# core_io3.net
KiCad netlist of a schematic drawn in EAGLE
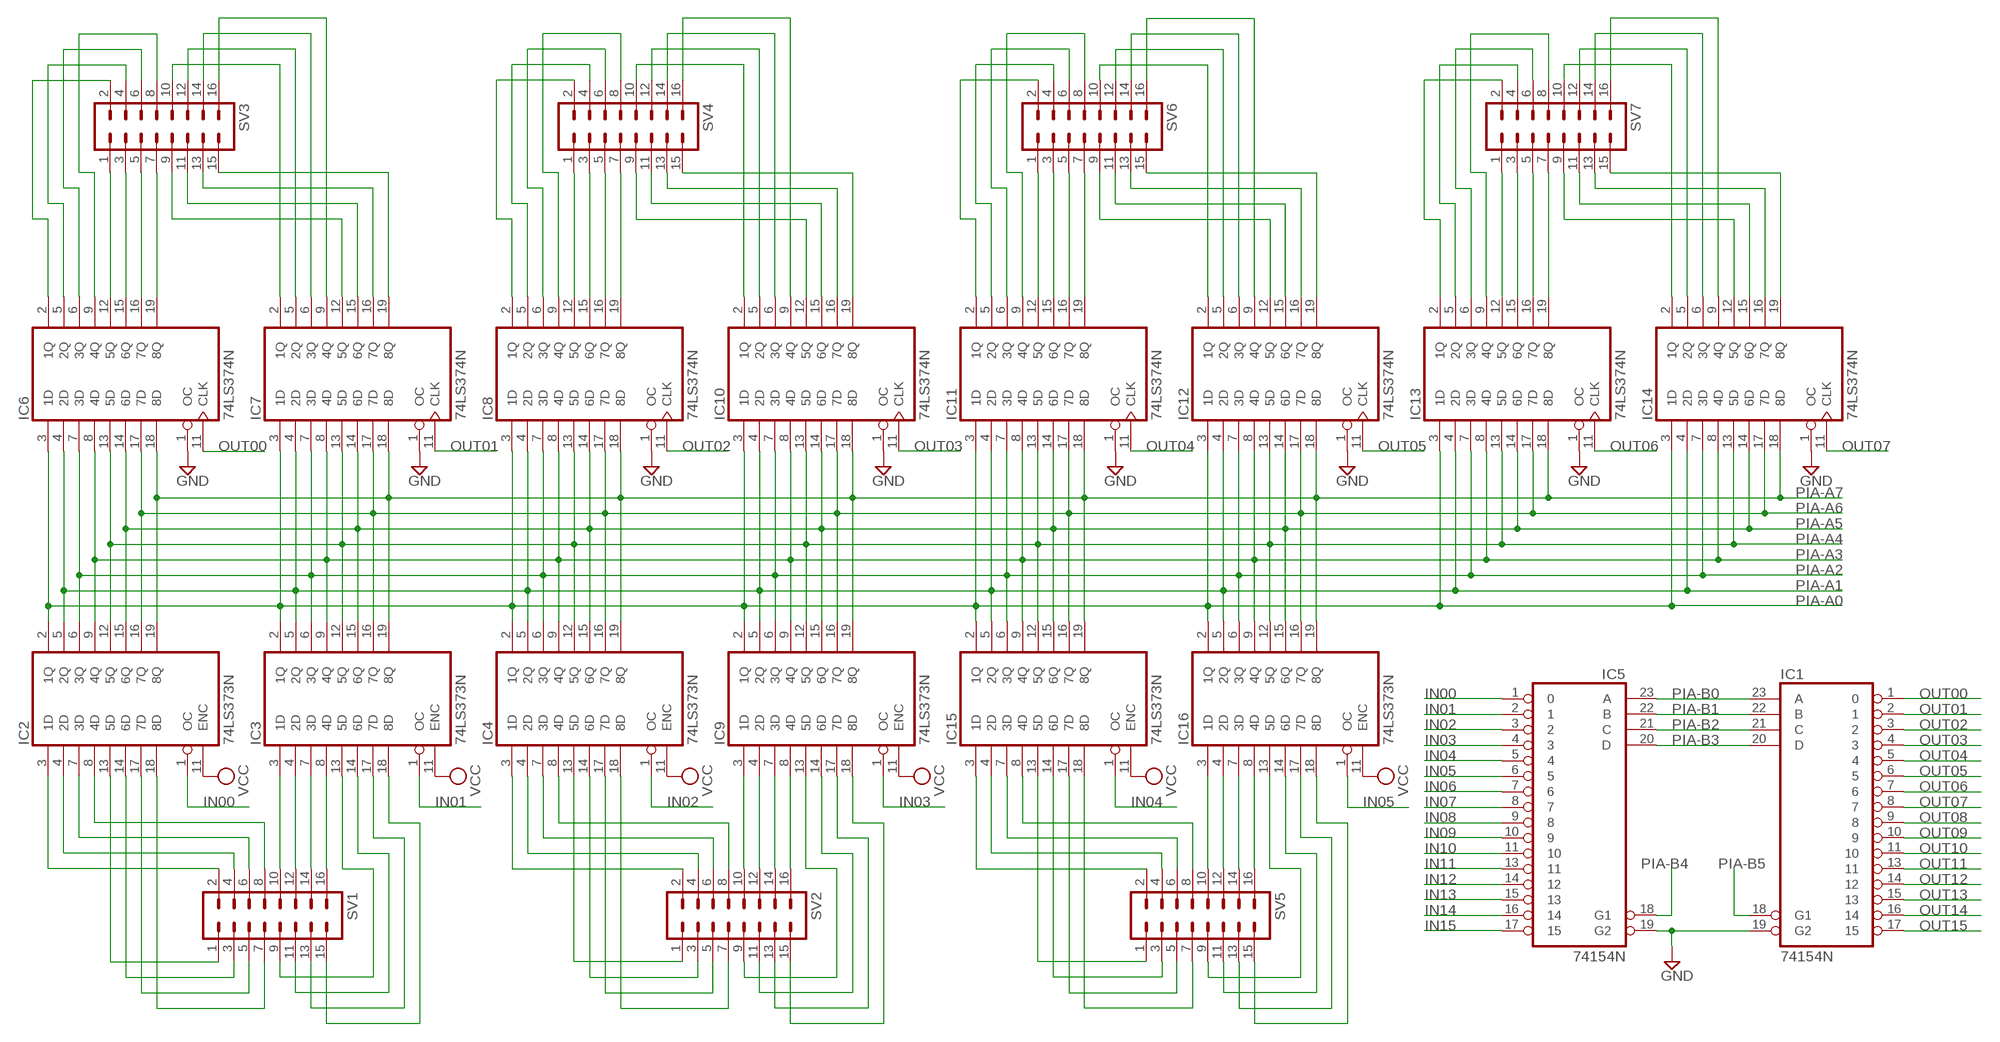
[diagram p0: schematic, sheet 1]
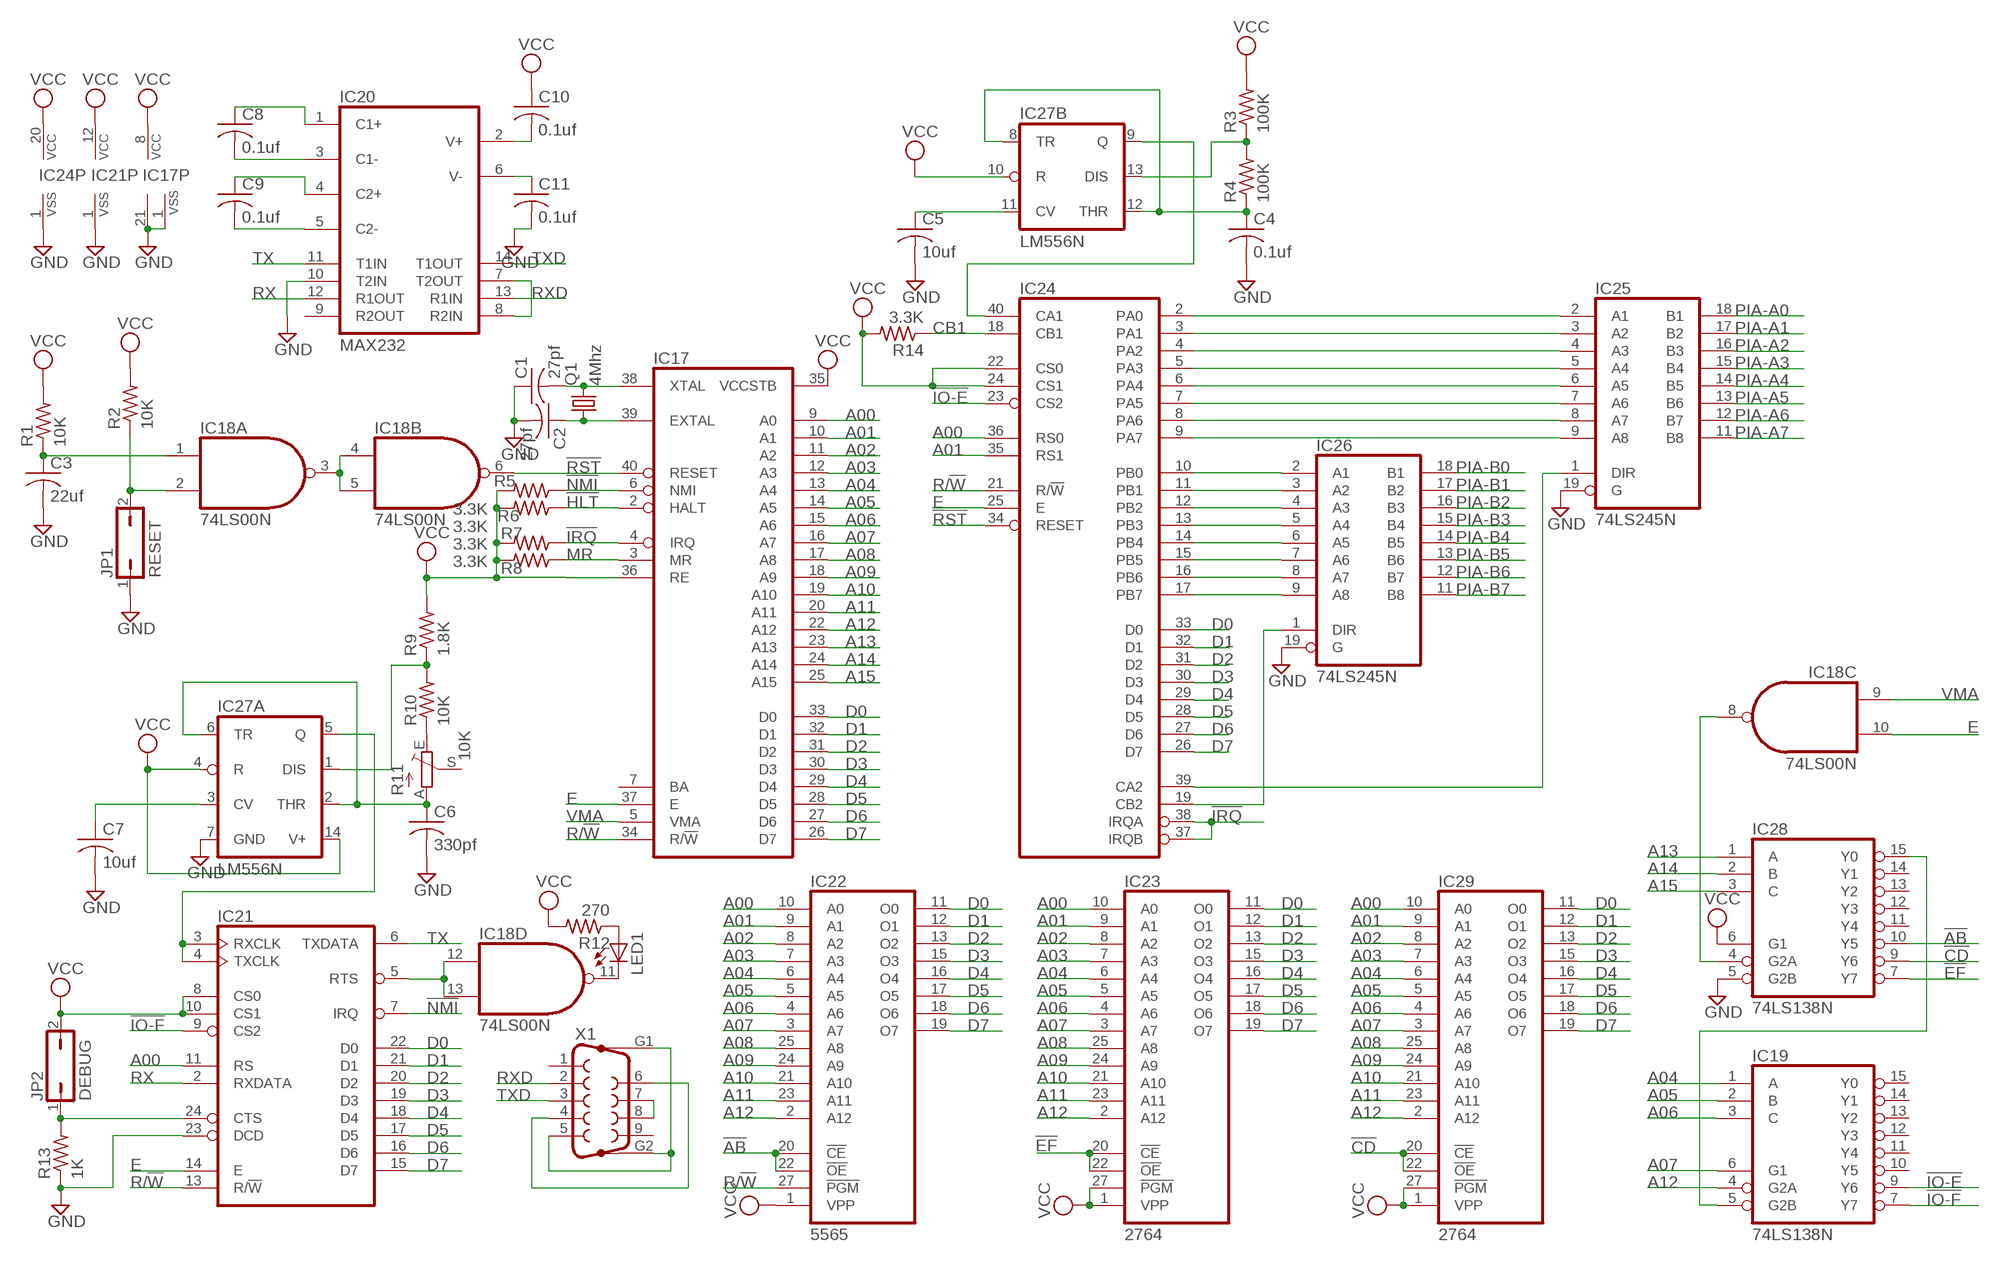
[diagram p1: schematic, sheet 2]
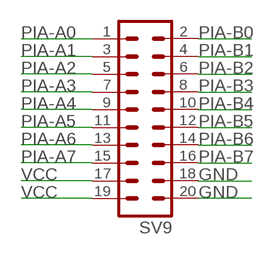
[diagram p2: schematic, sheet 3]

(export (version "E")
  (design (tool "Eeschema 10.0.6"))
  (components
    (comp (ref "C1")
      (value "27pf")
      (footprint "eagle-import:C050-025X075")
      (libsource (lib "eagle-import") (part "C-US050-025X075"))
    )
    (comp (ref "C2")
      (value "27pf")
      (footprint "eagle-import:C050-025X075")
      (libsource (lib "eagle-import") (part "C-US050-025X075"))
    )
    (comp (ref "C3")
      (value "22uf")
      (footprint "eagle-import:C102-043X133")
      (libsource (lib "eagle-import") (part "C-US102-043X133"))
    )
    (comp (ref "C4")
      (value "0.1uf")
      (footprint "eagle-import:C050-025X075")
      (libsource (lib "eagle-import") (part "C-US050-025X075"))
    )
    (comp (ref "C5")
      (value "10uf")
      (footprint "eagle-import:C050-025X075")
      (libsource (lib "eagle-import") (part "C-US050-025X075"))
    )
    (comp (ref "C6")
      (value "330pf")
      (footprint "eagle-import:C050-025X075")
      (libsource (lib "eagle-import") (part "C-US050-025X075"))
    )
    (comp (ref "C7")
      (value "10uf")
      (footprint "eagle-import:C050-025X075")
      (libsource (lib "eagle-import") (part "C-US050-025X075"))
    )
    (comp (ref "C8")
      (value "0.1uf")
      (footprint "eagle-import:C050-025X075")
      (libsource (lib "eagle-import") (part "C-US050-025X075"))
    )
    (comp (ref "C9")
      (value "0.1uf")
      (footprint "eagle-import:C050-025X075")
      (libsource (lib "eagle-import") (part "C-US050-025X075"))
    )
    (comp (ref "C10")
      (value "0.1uf")
      (footprint "eagle-import:C050-025X075")
      (libsource (lib "eagle-import") (part "C-US050-025X075"))
    )
    (comp (ref "C11")
      (value "0.1uf")
      (footprint "eagle-import:C050-025X075")
      (libsource (lib "eagle-import") (part "C-US050-025X075"))
    )
    (comp (ref "IC17")
      (value "6802")
      (footprint "eagle-import:DIL40")
      (libsource (lib "eagle-import") (part "6802"))
    )
    (comp (ref "IC18")
      (value "74LS00N")
      (footprint "eagle-import:DIL14")
      (libsource (lib "eagle-import") (part "7400NLS"))
    )
    (comp (ref "IC19")
      (value "74LS138N")
      (footprint "eagle-import:DIL16")
      (libsource (lib "eagle-import") (part "74138NLS"))
    )
    (comp (ref "IC20")
      (value "MAX232")
      (footprint "eagle-import:DIL16")
      (fields (field (name "MF") "MAXIM") (field (name "MPN") "MAX232ACPE+"))
      (libsource (lib "eagle-import") (part "MAX232"))
    )
    (comp (ref "IC21")
      (value "6850")
      (footprint "eagle-import:DIL24")
      (fields (field (name "MF") "NTE ELECTRONICS") (field (name "MPN") "NTE6850"))
      (libsource (lib "eagle-import") (part "6850"))
    )
    (comp (ref "IC22")
      (value "5565")
      (footprint "eagle-import:DIL28")
      (libsource (lib "eagle-import") (part "2764"))
    )
    (comp (ref "IC23")
      (value "2764")
      (footprint "eagle-import:DIL28")
      (libsource (lib "eagle-import") (part "2764"))
    )
    (comp (ref "IC24")
      (value "6821")
      (footprint "eagle-import:DIL40")
      (fields (field (name "MF") "NTE ELECTRONICS") (field (name "MPN") "NTE6821"))
      (libsource (lib "eagle-import") (part "6821"))
    )
    (comp (ref "IC25")
      (value "74LS245N")
      (footprint "eagle-import:DIL20")
      (libsource (lib "eagle-import") (part "74245NLS"))
    )
    (comp (ref "IC26")
      (value "74LS245N")
      (footprint "eagle-import:DIL20")
      (libsource (lib "eagle-import") (part "74245NLS"))
    )
    (comp (ref "IC27")
      (value "LM556N")
      (footprint "eagle-import:DIL14")
      (libsource (lib "eagle-import") (part "556NLM"))
    )
    (comp (ref "IC28")
      (value "74LS138N")
      (footprint "eagle-import:DIL16")
      (libsource (lib "eagle-import") (part "74138NLS"))
    )
    (comp (ref "IC29")
      (value "2764")
      (footprint "eagle-import:DIL28")
      (libsource (lib "eagle-import") (part "2764"))
    )
    (comp (ref "JP1")
      (value "RESET")
      (footprint "eagle-import:JP1")
      (libsource (lib "eagle-import") (part "JP1Q"))
    )
    (comp (ref "JP2")
      (value "DEBUG")
      (footprint "eagle-import:JP1")
      (libsource (lib "eagle-import") (part "JP1Q"))
    )
    (comp (ref "LED1")
      (value "LED3MM")
      (footprint "eagle-import:LED3MM")
      (libsource (lib "eagle-import") (part "LED3MM"))
    )
    (comp (ref "Q1")
      (value "4Mhz")
      (footprint "eagle-import:HC18U-V")
      (libsource (lib "eagle-import") (part "CRYSTALHC18U-V"))
    )
    (comp (ref "R1")
      (value "10K")
      (footprint "eagle-import:0207_7")
      (libsource (lib "eagle-import") (part "R-US_0207/7"))
    )
    (comp (ref "R2")
      (value "10K")
      (footprint "eagle-import:0207_7")
      (libsource (lib "eagle-import") (part "R-US_0207/7"))
    )
    (comp (ref "R3")
      (value "100K")
      (footprint "eagle-import:0207_7")
      (libsource (lib "eagle-import") (part "R-US_0207/7"))
    )
    (comp (ref "R4")
      (value "100K")
      (footprint "eagle-import:0207_7")
      (libsource (lib "eagle-import") (part "R-US_0207/7"))
    )
    (comp (ref "R5")
      (value "3.3K")
      (footprint "eagle-import:0207_7")
      (libsource (lib "eagle-import") (part "R-US_0207/7"))
    )
    (comp (ref "R6")
      (value "3.3K")
      (footprint "eagle-import:0207_7")
      (libsource (lib "eagle-import") (part "R-US_0207/7"))
    )
    (comp (ref "R7")
      (value "3.3K")
      (footprint "eagle-import:0207_7")
      (libsource (lib "eagle-import") (part "R-US_0207/7"))
    )
    (comp (ref "R8")
      (value "3.3K")
      (footprint "eagle-import:0207_7")
      (libsource (lib "eagle-import") (part "R-US_0207/7"))
    )
    (comp (ref "R9")
      (value "1.8K")
      (footprint "eagle-import:0207_7")
      (libsource (lib "eagle-import") (part "R-US_0207/7"))
    )
    (comp (ref "R10")
      (value "10K")
      (footprint "eagle-import:0207_7")
      (libsource (lib "eagle-import") (part "R-US_0207/7"))
    )
    (comp (ref "R11")
      (value "10K")
      (footprint "eagle-import:SP19L")
      (libsource (lib "eagle-import") (part "TRIM_EU-B90P"))
    )
    (comp (ref "R12")
      (value "270")
      (footprint "eagle-import:0207_7")
      (libsource (lib "eagle-import") (part "R-US_0207/7"))
    )
    (comp (ref "R13")
      (value "1K")
      (footprint "eagle-import:0207_7")
      (libsource (lib "eagle-import") (part "R-US_0207/7"))
    )
    (comp (ref "R14")
      (value "3.3K")
      (footprint "eagle-import:0207_7")
      (libsource (lib "eagle-import") (part "R-US_0207/7"))
    )
    (comp (ref "X1")
      (value "F09HP")
      (footprint "eagle-import:F09HP")
      (libsource (lib "eagle-import") (part "F09HP"))
    )
    (comp (ref "IC1")
      (value "74154N")
      (footprint "eagle-import:DIL24-6")
      (libsource (lib "eagle-import") (part "74154N"))
    )
    (comp (ref "IC2")
      (value "74LS373N")
      (footprint "eagle-import:DIL20")
      (libsource (lib "eagle-import") (part "74373NLS"))
    )
    (comp (ref "IC3")
      (value "74LS373N")
      (footprint "eagle-import:DIL20")
      (libsource (lib "eagle-import") (part "74373NLS"))
    )
    (comp (ref "IC4")
      (value "74LS373N")
      (footprint "eagle-import:DIL20")
      (libsource (lib "eagle-import") (part "74373NLS"))
    )
    (comp (ref "IC5")
      (value "74154N")
      (footprint "eagle-import:DIL24-6")
      (libsource (lib "eagle-import") (part "74154N"))
    )
    (comp (ref "IC6")
      (value "74LS374N")
      (footprint "eagle-import:DIL20")
      (libsource (lib "eagle-import") (part "74374NLS"))
    )
    (comp (ref "IC7")
      (value "74LS374N")
      (footprint "eagle-import:DIL20")
      (libsource (lib "eagle-import") (part "74374NLS"))
    )
    (comp (ref "IC8")
      (value "74LS374N")
      (footprint "eagle-import:DIL20")
      (libsource (lib "eagle-import") (part "74374NLS"))
    )
    (comp (ref "IC9")
      (value "74LS373N")
      (footprint "eagle-import:DIL20")
      (libsource (lib "eagle-import") (part "74373NLS"))
    )
    (comp (ref "IC10")
      (value "74LS374N")
      (footprint "eagle-import:DIL20")
      (libsource (lib "eagle-import") (part "74374NLS"))
    )
    (comp (ref "IC11")
      (value "74LS374N")
      (footprint "eagle-import:DIL20")
      (libsource (lib "eagle-import") (part "74374NLS"))
    )
    (comp (ref "IC12")
      (value "74LS374N")
      (footprint "eagle-import:DIL20")
      (libsource (lib "eagle-import") (part "74374NLS"))
    )
    (comp (ref "IC13")
      (value "74LS374N")
      (footprint "eagle-import:DIL20")
      (libsource (lib "eagle-import") (part "74374NLS"))
    )
    (comp (ref "IC14")
      (value "74LS374N")
      (footprint "eagle-import:DIL20")
      (libsource (lib "eagle-import") (part "74374NLS"))
    )
    (comp (ref "IC15")
      (value "74LS373N")
      (footprint "eagle-import:DIL20")
      (libsource (lib "eagle-import") (part "74373NLS"))
    )
    (comp (ref "IC16")
      (value "74LS373N")
      (footprint "eagle-import:DIL20")
      (libsource (lib "eagle-import") (part "74373NLS"))
    )
    (comp (ref "SV1")
      (value "MA08-2")
      (footprint "eagle-import:MA08-2")
      (libsource (lib "eagle-import") (part "MA08-2"))
    )
    (comp (ref "SV2")
      (value "MA08-2")
      (footprint "eagle-import:MA08-2")
      (libsource (lib "eagle-import") (part "MA08-2"))
    )
    (comp (ref "SV3")
      (value "MA08-2")
      (footprint "eagle-import:MA08-2")
      (libsource (lib "eagle-import") (part "MA08-2"))
    )
    (comp (ref "SV4")
      (value "MA08-2")
      (footprint "eagle-import:MA08-2")
      (libsource (lib "eagle-import") (part "MA08-2"))
    )
    (comp (ref "SV5")
      (value "MA08-2")
      (footprint "eagle-import:MA08-2")
      (libsource (lib "eagle-import") (part "MA08-2"))
    )
    (comp (ref "SV6")
      (value "MA08-2")
      (footprint "eagle-import:MA08-2")
      (libsource (lib "eagle-import") (part "MA08-2"))
    )
    (comp (ref "SV7")
      (value "MA08-2")
      (footprint "eagle-import:MA08-2")
      (libsource (lib "eagle-import") (part "MA08-2"))
    )
    (comp (ref "SV9")
      (value "MA10-2")
      (footprint "eagle-import:MA10-2")
      (libsource (lib "eagle-import") (part "MA10-2"))
    )
  )
  (nets
    (net (code "1") (name "A00") (class "Default")
      (node (ref "IC17") (pin "9") (pinfunction "A0_9") (pintype "output"))
      (node (ref "IC21") (pin "11") (pinfunction "RS_11") (pintype "input"))
      (node (ref "IC22") (pin "10") (pinfunction "A0_10") (pintype "input"))
      (node (ref "IC23") (pin "10") (pinfunction "A0_10") (pintype "input"))
      (node (ref "IC24") (pin "36") (pinfunction "RS0_36") (pintype "input"))
      (node (ref "IC29") (pin "10") (pinfunction "A0_10") (pintype "input"))
    )
    (net (code "2") (name "A01") (class "Default")
      (node (ref "IC17") (pin "10") (pinfunction "A1_10") (pintype "output"))
      (node (ref "IC22") (pin "9") (pinfunction "A1_9") (pintype "input"))
      (node (ref "IC23") (pin "9") (pinfunction "A1_9") (pintype "input"))
      (node (ref "IC24") (pin "35") (pinfunction "RS1_35") (pintype "input"))
      (node (ref "IC29") (pin "9") (pinfunction "A1_9") (pintype "input"))
    )
    (net (code "3") (name "A02") (class "Default")
      (node (ref "IC17") (pin "11") (pinfunction "A2_11") (pintype "output"))
      (node (ref "IC22") (pin "8") (pinfunction "A2_8") (pintype "input"))
      (node (ref "IC23") (pin "8") (pinfunction "A2_8") (pintype "input"))
      (node (ref "IC29") (pin "8") (pinfunction "A2_8") (pintype "input"))
    )
    (net (code "4") (name "A03") (class "Default")
      (node (ref "IC17") (pin "12") (pinfunction "A3_12") (pintype "output"))
      (node (ref "IC22") (pin "7") (pinfunction "A3_7") (pintype "input"))
      (node (ref "IC23") (pin "7") (pinfunction "A3_7") (pintype "input"))
      (node (ref "IC29") (pin "7") (pinfunction "A3_7") (pintype "input"))
    )
    (net (code "5") (name "A04") (class "Default")
      (node (ref "IC17") (pin "13") (pinfunction "A4_13") (pintype "output"))
      (node (ref "IC19") (pin "1") (pinfunction "A_1") (pintype "input"))
      (node (ref "IC22") (pin "6") (pinfunction "A4_6") (pintype "input"))
      (node (ref "IC23") (pin "6") (pinfunction "A4_6") (pintype "input"))
      (node (ref "IC29") (pin "6") (pinfunction "A4_6") (pintype "input"))
    )
    (net (code "6") (name "A05") (class "Default")
      (node (ref "IC17") (pin "14") (pinfunction "A5_14") (pintype "output"))
      (node (ref "IC19") (pin "2") (pinfunction "B_2") (pintype "input"))
      (node (ref "IC22") (pin "5") (pinfunction "A5_5") (pintype "input"))
      (node (ref "IC23") (pin "5") (pinfunction "A5_5") (pintype "input"))
      (node (ref "IC29") (pin "5") (pinfunction "A5_5") (pintype "input"))
    )
    (net (code "7") (name "A06") (class "Default")
      (node (ref "IC17") (pin "15") (pinfunction "A6_15") (pintype "output"))
      (node (ref "IC19") (pin "3") (pinfunction "C_3") (pintype "input"))
      (node (ref "IC22") (pin "4") (pinfunction "A6_4") (pintype "input"))
      (node (ref "IC23") (pin "4") (pinfunction "A6_4") (pintype "input"))
      (node (ref "IC29") (pin "4") (pinfunction "A6_4") (pintype "input"))
    )
    (net (code "8") (name "A07") (class "Default")
      (node (ref "IC17") (pin "16") (pinfunction "A7_16") (pintype "output"))
      (node (ref "IC19") (pin "6") (pinfunction "G1_6") (pintype "input"))
      (node (ref "IC22") (pin "3") (pinfunction "A7_3") (pintype "input"))
      (node (ref "IC23") (pin "3") (pinfunction "A7_3") (pintype "input"))
      (node (ref "IC29") (pin "3") (pinfunction "A7_3") (pintype "input"))
    )
    (net (code "9") (name "A08") (class "Default")
      (node (ref "IC17") (pin "17") (pinfunction "A8_17") (pintype "output"))
      (node (ref "IC22") (pin "25") (pinfunction "A8_25") (pintype "input"))
      (node (ref "IC23") (pin "25") (pinfunction "A8_25") (pintype "input"))
      (node (ref "IC29") (pin "25") (pinfunction "A8_25") (pintype "input"))
    )
    (net (code "10") (name "A09") (class "Default")
      (node (ref "IC17") (pin "18") (pinfunction "A9_18") (pintype "output"))
      (node (ref "IC22") (pin "24") (pinfunction "A9_24") (pintype "input"))
      (node (ref "IC23") (pin "24") (pinfunction "A9_24") (pintype "input"))
      (node (ref "IC29") (pin "24") (pinfunction "A9_24") (pintype "input"))
    )
    (net (code "11") (name "A10") (class "Default")
      (node (ref "IC17") (pin "19") (pinfunction "A10_19") (pintype "output"))
      (node (ref "IC22") (pin "21") (pinfunction "A10_21") (pintype "input"))
      (node (ref "IC23") (pin "21") (pinfunction "A10_21") (pintype "input"))
      (node (ref "IC29") (pin "21") (pinfunction "A10_21") (pintype "input"))
    )
    (net (code "12") (name "A11") (class "Default")
      (node (ref "IC17") (pin "20") (pinfunction "A11_20") (pintype "output"))
      (node (ref "IC22") (pin "23") (pinfunction "A11_23") (pintype "input"))
      (node (ref "IC23") (pin "23") (pinfunction "A11_23") (pintype "input"))
      (node (ref "IC29") (pin "23") (pinfunction "A11_23") (pintype "input"))
    )
    (net (code "13") (name "A12") (class "Default")
      (node (ref "IC17") (pin "22") (pinfunction "A12_22") (pintype "output"))
      (node (ref "IC19") (pin "4") (pinfunction "G2A_4") (pintype "input"))
      (node (ref "IC22") (pin "2") (pinfunction "A12_2") (pintype "input"))
      (node (ref "IC23") (pin "2") (pinfunction "A12_2") (pintype "input"))
      (node (ref "IC29") (pin "2") (pinfunction "A12_2") (pintype "input"))
    )
    (net (code "14") (name "A13") (class "Default")
      (node (ref "IC17") (pin "23") (pinfunction "A13_23") (pintype "output"))
      (node (ref "IC28") (pin "1") (pinfunction "A_1") (pintype "input"))
    )
    (net (code "15") (name "A14") (class "Default")
      (node (ref "IC17") (pin "24") (pinfunction "A14_24") (pintype "output"))
      (node (ref "IC28") (pin "2") (pinfunction "B_2") (pintype "input"))
    )
    (net (code "16") (name "A15") (class "Default")
      (node (ref "IC17") (pin "25") (pinfunction "A15_25") (pintype "output"))
      (node (ref "IC28") (pin "3") (pinfunction "C_3") (pintype "input"))
    )
    (net (code "17") (name "CB1") (class "Default")
      (node (ref "IC24") (pin "18") (pinfunction "CB1_18") (pintype "input"))
      (node (ref "R14") (pin "1") (pinfunction "1_1") (pintype "passive"))
    )
    (net (code "18") (name "D0") (class "Default")
      (node (ref "IC17") (pin "33") (pinfunction "D0_33") (pintype "bidirectional"))
      (node (ref "IC21") (pin "22") (pinfunction "D0_22") (pintype "bidirectional"))
      (node (ref "IC22") (pin "11") (pinfunction "O0_11") (pintype "tri_state"))
      (node (ref "IC23") (pin "11") (pinfunction "O0_11") (pintype "tri_state"))
      (node (ref "IC24") (pin "33") (pinfunction "D0_33") (pintype "bidirectional"))
      (node (ref "IC29") (pin "11") (pinfunction "O0_11") (pintype "tri_state"))
    )
    (net (code "19") (name "D1") (class "Default")
      (node (ref "IC17") (pin "32") (pinfunction "D1_32") (pintype "bidirectional"))
      (node (ref "IC21") (pin "21") (pinfunction "D1_21") (pintype "bidirectional"))
      (node (ref "IC22") (pin "12") (pinfunction "O1_12") (pintype "tri_state"))
      (node (ref "IC23") (pin "12") (pinfunction "O1_12") (pintype "tri_state"))
      (node (ref "IC24") (pin "32") (pinfunction "D1_32") (pintype "bidirectional"))
      (node (ref "IC29") (pin "12") (pinfunction "O1_12") (pintype "tri_state"))
    )
    (net (code "20") (name "D2") (class "Default")
      (node (ref "IC17") (pin "31") (pinfunction "D2_31") (pintype "bidirectional"))
      (node (ref "IC21") (pin "20") (pinfunction "D2_20") (pintype "bidirectional"))
      (node (ref "IC22") (pin "13") (pinfunction "O2_13") (pintype "tri_state"))
      (node (ref "IC23") (pin "13") (pinfunction "O2_13") (pintype "tri_state"))
      (node (ref "IC24") (pin "31") (pinfunction "D2_31") (pintype "bidirectional"))
      (node (ref "IC29") (pin "13") (pinfunction "O2_13") (pintype "tri_state"))
    )
    (net (code "21") (name "D3") (class "Default")
      (node (ref "IC17") (pin "30") (pinfunction "D3_30") (pintype "bidirectional"))
      (node (ref "IC21") (pin "19") (pinfunction "D3_19") (pintype "bidirectional"))
      (node (ref "IC22") (pin "15") (pinfunction "O3_15") (pintype "tri_state"))
      (node (ref "IC23") (pin "15") (pinfunction "O3_15") (pintype "tri_state"))
      (node (ref "IC24") (pin "30") (pinfunction "D3_30") (pintype "bidirectional"))
      (node (ref "IC29") (pin "15") (pinfunction "O3_15") (pintype "tri_state"))
    )
    (net (code "22") (name "D4") (class "Default")
      (node (ref "IC17") (pin "29") (pinfunction "D4_29") (pintype "bidirectional"))
      (node (ref "IC21") (pin "18") (pinfunction "D4_18") (pintype "bidirectional"))
      (node (ref "IC22") (pin "16") (pinfunction "O4_16") (pintype "tri_state"))
      (node (ref "IC23") (pin "16") (pinfunction "O4_16") (pintype "tri_state"))
      (node (ref "IC24") (pin "29") (pinfunction "D4_29") (pintype "bidirectional"))
      (node (ref "IC29") (pin "16") (pinfunction "O4_16") (pintype "tri_state"))
    )
    (net (code "23") (name "D5") (class "Default")
      (node (ref "IC17") (pin "28") (pinfunction "D5_28") (pintype "bidirectional"))
      (node (ref "IC21") (pin "17") (pinfunction "D5_17") (pintype "bidirectional"))
      (node (ref "IC22") (pin "17") (pinfunction "O5_17") (pintype "tri_state"))
      (node (ref "IC23") (pin "17") (pinfunction "O5_17") (pintype "tri_state"))
      (node (ref "IC24") (pin "28") (pinfunction "D5_28") (pintype "bidirectional"))
      (node (ref "IC29") (pin "17") (pinfunction "O5_17") (pintype "tri_state"))
    )
    (net (code "24") (name "D6") (class "Default")
      (node (ref "IC17") (pin "27") (pinfunction "D6_27") (pintype "bidirectional"))
      (node (ref "IC21") (pin "16") (pinfunction "D6_16") (pintype "bidirectional"))
      (node (ref "IC22") (pin "18") (pinfunction "O6_18") (pintype "tri_state"))
      (node (ref "IC23") (pin "18") (pinfunction "O6_18") (pintype "tri_state"))
      (node (ref "IC24") (pin "27") (pinfunction "D6_27") (pintype "bidirectional"))
      (node (ref "IC29") (pin "18") (pinfunction "O6_18") (pintype "tri_state"))
    )
    (net (code "25") (name "D7") (class "Default")
      (node (ref "IC17") (pin "26") (pinfunction "D7_26") (pintype "bidirectional"))
      (node (ref "IC21") (pin "15") (pinfunction "D7_15") (pintype "bidirectional"))
      (node (ref "IC22") (pin "19") (pinfunction "O7_19") (pintype "tri_state"))
      (node (ref "IC23") (pin "19") (pinfunction "O7_19") (pintype "tri_state"))
      (node (ref "IC24") (pin "26") (pinfunction "D7_26") (pintype "bidirectional"))
      (node (ref "IC29") (pin "19") (pinfunction "O7_19") (pintype "tri_state"))
    )
    (net (code "26") (name "E") (class "Default")
      (node (ref "IC17") (pin "37") (pinfunction "E_37") (pintype "output"))
      (node (ref "IC18") (pin "10") (pinfunction "I1_10") (pintype "input"))
      (node (ref "IC21") (pin "14") (pinfunction "E_14") (pintype "input"))
      (node (ref "IC24") (pin "25") (pinfunction "E_25") (pintype "input"))
    )
    (net (code "27") (name "GND") (class "Default")
      (node (ref "C1") (pin "1") (pinfunction "1_1") (pintype "passive"))
      (node (ref "C11") (pin "2") (pinfunction "2_2") (pintype "passive"))
      (node (ref "C2") (pin "2") (pinfunction "2_2") (pintype "passive"))
      (node (ref "C3") (pin "2") (pinfunction "2_2") (pintype "passive"))
      (node (ref "C4") (pin "2") (pinfunction "2_2") (pintype "passive"))
      (node (ref "C5") (pin "2") (pinfunction "2_2") (pintype "passive"))
      (node (ref "C6") (pin "2") (pinfunction "2_2") (pintype "passive"))
      (node (ref "C7") (pin "2") (pinfunction "2_2") (pintype "passive"))
      (node (ref "IC1") (pin "19") (pinfunction "G2_19") (pintype "input"))
      (node (ref "IC10") (pin "1") (pinfunction "OC_1") (pintype "input"))
      (node (ref "IC11") (pin "1") (pinfunction "OC_1") (pintype "input"))
      (node (ref "IC12") (pin "1") (pinfunction "OC_1") (pintype "input"))
      (node (ref "IC13") (pin "1") (pinfunction "OC_1") (pintype "input"))
      (node (ref "IC14") (pin "1") (pinfunction "OC_1") (pintype "input"))
      (node (ref "IC17") (pin "1") (pinfunction "VSS_1") (pintype "power_in"))
      (node (ref "IC17") (pin "21") (pinfunction "VSS_21") (pintype "power_in"))
      (node (ref "IC20") (pin "10") (pinfunction "T2IN_10") (pintype "input"))
      (node (ref "IC21") (pin "1") (pinfunction "VSS_1") (pintype "power_in"))
      (node (ref "IC21") (pin "23") (pinfunction "DCD_23") (pintype "input"))
      (node (ref "IC24") (pin "1") (pinfunction "VSS_1") (pintype "power_in"))
      (node (ref "IC25") (pin "19") (pinfunction "G_19") (pintype "input"))
      (node (ref "IC26") (pin "19") (pinfunction "G_19") (pintype "input"))
      (node (ref "IC27") (pin "7") (pinfunction "GND_7") (pintype "power_in"))
      (node (ref "IC28") (pin "5") (pinfunction "G2B_5") (pintype "input"))
      (node (ref "IC5") (pin "19") (pinfunction "G2_19") (pintype "input"))
      (node (ref "IC6") (pin "1") (pinfunction "OC_1") (pintype "input"))
      (node (ref "IC7") (pin "1") (pinfunction "OC_1") (pintype "input"))
      (node (ref "IC8") (pin "1") (pinfunction "OC_1") (pintype "input"))
      (node (ref "JP1") (pin "1") (pinfunction "1_1") (pintype "passive"))
      (node (ref "R13") (pin "1") (pinfunction "1_1") (pintype "passive"))
      (node (ref "SV9") (pin "18") (pinfunction "18_18") (pintype "passive"))
      (node (ref "SV9") (pin "20") (pinfunction "20_20") (pintype "passive"))
    )
    (net (code "28") (name "IN00") (class "Default")
      (node (ref "IC2") (pin "1") (pinfunction "OC_1") (pintype "input"))
      (node (ref "IC5") (pin "1") (pinfunction "0_1") (pintype "output"))
    )
    (net (code "29") (name "IN01") (class "Default")
      (node (ref "IC3") (pin "1") (pinfunction "OC_1") (pintype "input"))
      (node (ref "IC5") (pin "2") (pinfunction "1_2") (pintype "output"))
    )
    (net (code "30") (name "IN02") (class "Default")
      (node (ref "IC4") (pin "1") (pinfunction "OC_1") (pintype "input"))
      (node (ref "IC5") (pin "3") (pinfunction "2_3") (pintype "output"))
    )
    (net (code "31") (name "IN03") (class "Default")
      (node (ref "IC5") (pin "4") (pinfunction "3_4") (pintype "output"))
      (node (ref "IC9") (pin "1") (pinfunction "OC_1") (pintype "input"))
    )
    (net (code "32") (name "IN04") (class "Default")
      (node (ref "IC15") (pin "1") (pinfunction "OC_1") (pintype "input"))
      (node (ref "IC5") (pin "5") (pinfunction "4_5") (pintype "output"))
    )
    (net (code "33") (name "IN05") (class "Default")
      (node (ref "IC16") (pin "1") (pinfunction "OC_1") (pintype "input"))
      (node (ref "IC5") (pin "6") (pinfunction "5_6") (pintype "output"))
    )
    (net (code "34") (name "IN06") (class "Default")
      (node (ref "IC5") (pin "7") (pinfunction "6_7") (pintype "output"))
    )
    (net (code "35") (name "IN07") (class "Default")
      (node (ref "IC5") (pin "8") (pinfunction "7_8") (pintype "output"))
    )
    (net (code "36") (name "IN08") (class "Default")
      (node (ref "IC5") (pin "9") (pinfunction "8_9") (pintype "output"))
    )
    (net (code "37") (name "IN09") (class "Default")
      (node (ref "IC5") (pin "10") (pinfunction "9_10") (pintype "output"))
    )
    (net (code "38") (name "IN10") (class "Default")
      (node (ref "IC5") (pin "11") (pinfunction "10_11") (pintype "output"))
    )
    (net (code "39") (name "IN11") (class "Default")
      (node (ref "IC5") (pin "13") (pinfunction "11_13") (pintype "output"))
    )
    (net (code "40") (name "IN12") (class "Default")
      (node (ref "IC5") (pin "14") (pinfunction "12_14") (pintype "output"))
    )
    (net (code "41") (name "IN13") (class "Default")
      (node (ref "IC5") (pin "15") (pinfunction "13_15") (pintype "output"))
    )
    (net (code "42") (name "IN14") (class "Default")
      (node (ref "IC5") (pin "16") (pinfunction "14_16") (pintype "output"))
    )
    (net (code "43") (name "IN15") (class "Default")
      (node (ref "IC5") (pin "17") (pinfunction "15_17") (pintype "output"))
    )
    (net (code "44") (name "MR") (class "Default")
      (node (ref "IC17") (pin "3") (pinfunction "MR_3") (pintype "input"))
      (node (ref "R8") (pin "1") (pinfunction "1_1") (pintype "passive"))
    )
    (net (code "45") (name "Net-(IC2A-1D)") (class "Default")
      (node (ref "IC2") (pin "3") (pinfunction "1D_3") (pintype "input"))
      (node (ref "SV1") (pin "2") (pinfunction "2_2") (pintype "passive"))
    )
    (net (code "46") (name "Net-(IC2A-2D)") (class "Default")
      (node (ref "IC2") (pin "4") (pinfunction "2D_4") (pintype "input"))
      (node (ref "SV1") (pin "4") (pinfunction "4_4") (pintype "passive"))
    )
    (net (code "47") (name "Net-(IC2A-3D)") (class "Default")
      (node (ref "IC2") (pin "7") (pinfunction "3D_7") (pintype "input"))
      (node (ref "SV1") (pin "6") (pinfunction "6_6") (pintype "passive"))
    )
    (net (code "48") (name "Net-(IC2A-4D)") (class "Default")
      (node (ref "IC2") (pin "8") (pinfunction "4D_8") (pintype "input"))
      (node (ref "SV1") (pin "8") (pinfunction "8_8") (pintype "passive"))
    )
    (net (code "49") (name "Net-(IC2A-5D)") (class "Default")
      (node (ref "IC2") (pin "13") (pinfunction "5D_13") (pintype "input"))
      (node (ref "SV1") (pin "1") (pinfunction "1_1") (pintype "passive"))
    )
    (net (code "50") (name "Net-(IC2A-6D)") (class "Default")
      (node (ref "IC2") (pin "14") (pinfunction "6D_14") (pintype "input"))
      (node (ref "SV1") (pin "3") (pinfunction "3_3") (pintype "passive"))
    )
    (net (code "51") (name "Net-(IC2A-7D)") (class "Default")
      (node (ref "IC2") (pin "17") (pinfunction "7D_17") (pintype "input"))
      (node (ref "SV1") (pin "5") (pinfunction "5_5") (pintype "passive"))
    )
    (net (code "52") (name "Net-(IC2A-8D)") (class "Default")
      (node (ref "IC2") (pin "18") (pinfunction "8D_18") (pintype "input"))
      (node (ref "SV1") (pin "7") (pinfunction "7_7") (pintype "passive"))
    )
    (net (code "53") (name "Net-(IC3A-1D)") (class "Default")
      (node (ref "IC3") (pin "3") (pinfunction "1D_3") (pintype "input"))
      (node (ref "SV1") (pin "10") (pinfunction "10_10") (pintype "passive"))
    )
    (net (code "54") (name "Net-(IC3A-2D)") (class "Default")
      (node (ref "IC3") (pin "4") (pinfunction "2D_4") (pintype "input"))
      (node (ref "SV1") (pin "12") (pinfunction "12_12") (pintype "passive"))
    )
    (net (code "55") (name "Net-(IC3A-3D)") (class "Default")
      (node (ref "IC3") (pin "7") (pinfunction "3D_7") (pintype "input"))
      (node (ref "SV1") (pin "14") (pinfunction "14_14") (pintype "passive"))
    )
    (net (code "56") (name "Net-(IC3A-4D)") (class "Default")
      (node (ref "IC3") (pin "8") (pinfunction "4D_8") (pintype "input"))
      (node (ref "SV1") (pin "16") (pinfunction "16_16") (pintype "passive"))
    )
    (net (code "57") (name "Net-(IC3A-5D)") (class "Default")
      (node (ref "IC3") (pin "13") (pinfunction "5D_13") (pintype "input"))
      (node (ref "SV1") (pin "9") (pinfunction "9_9") (pintype "passive"))
    )
    (net (code "58") (name "Net-(IC3A-6D)") (class "Default")
      (node (ref "IC3") (pin "14") (pinfunction "6D_14") (pintype "input"))
      (node (ref "SV1") (pin "11") (pinfunction "11_11") (pintype "passive"))
    )
    (net (code "59") (name "Net-(IC3A-7D)") (class "Default")
      (node (ref "IC3") (pin "17") (pinfunction "7D_17") (pintype "input"))
      (node (ref "SV1") (pin "13") (pinfunction "13_13") (pintype "passive"))
    )
    (net (code "60") (name "Net-(IC3A-8D)") (class "Default")
      (node (ref "IC3") (pin "18") (pinfunction "8D_18") (pintype "input"))
      (node (ref "SV1") (pin "15") (pinfunction "15_15") (pintype "passive"))
    )
    (net (code "61") (name "Net-(IC4A-1D)") (class "Default")
      (node (ref "IC4") (pin "3") (pinfunction "1D_3") (pintype "input"))
      (node (ref "SV2") (pin "2") (pinfunction "2_2") (pintype "passive"))
    )
    (net (code "62") (name "Net-(IC4A-2D)") (class "Default")
      (node (ref "IC4") (pin "4") (pinfunction "2D_4") (pintype "input"))
      (node (ref "SV2") (pin "4") (pinfunction "4_4") (pintype "passive"))
    )
    (net (code "63") (name "Net-(IC4A-3D)") (class "Default")
      (node (ref "IC4") (pin "7") (pinfunction "3D_7") (pintype "input"))
      (node (ref "SV2") (pin "6") (pinfunction "6_6") (pintype "passive"))
    )
    (net (code "64") (name "Net-(IC4A-4D)") (class "Default")
      (node (ref "IC4") (pin "8") (pinfunction "4D_8") (pintype "input"))
      (node (ref "SV2") (pin "8") (pinfunction "8_8") (pintype "passive"))
    )
    (net (code "65") (name "Net-(IC4A-5D)") (class "Default")
      (node (ref "IC4") (pin "13") (pinfunction "5D_13") (pintype "input"))
      (node (ref "SV2") (pin "1") (pinfunction "1_1") (pintype "passive"))
    )
    (net (code "66") (name "Net-(IC4A-6D)") (class "Default")
      (node (ref "IC4") (pin "14") (pinfunction "6D_14") (pintype "input"))
      (node (ref "SV2") (pin "3") (pinfunction "3_3") (pintype "passive"))
    )
    (net (code "67") (name "Net-(IC4A-7D)") (class "Default")
      (node (ref "IC4") (pin "17") (pinfunction "7D_17") (pintype "input"))
      (node (ref "SV2") (pin "5") (pinfunction "5_5") (pintype "passive"))
    )
    (net (code "68") (name "Net-(IC4A-8D)") (class "Default")
      (node (ref "IC4") (pin "18") (pinfunction "8D_18") (pintype "input"))
      (node (ref "SV2") (pin "7") (pinfunction "7_7") (pintype "passive"))
    )
    (net (code "69") (name "Net-(IC6A-1Q)") (class "Default")
      (node (ref "IC6") (pin "2") (pinfunction "1Q_2") (pintype "tri_state"))
      (node (ref "SV3") (pin "2") (pinfunction "2_2") (pintype "passive"))
    )
    (net (code "70") (name "Net-(IC6A-2Q)") (class "Default")
      (node (ref "IC6") (pin "5") (pinfunction "2Q_5") (pintype "tri_state"))
      (node (ref "SV3") (pin "4") (pinfunction "4_4") (pintype "passive"))
    )
    (net (code "71") (name "Net-(IC6A-3Q)") (class "Default")
      (node (ref "IC6") (pin "6") (pinfunction "3Q_6") (pintype "tri_state"))
      (node (ref "SV3") (pin "6") (pinfunction "6_6") (pintype "passive"))
    )
    (net (code "72") (name "Net-(IC6A-4Q)") (class "Default")
      (node (ref "IC6") (pin "9") (pinfunction "4Q_9") (pintype "tri_state"))
      (node (ref "SV3") (pin "8") (pinfunction "8_8") (pintype "passive"))
    )
    (net (code "73") (name "Net-(IC6A-5Q)") (class "Default")
      (node (ref "IC6") (pin "12") (pinfunction "5Q_12") (pintype "tri_state"))
      (node (ref "SV3") (pin "1") (pinfunction "1_1") (pintype "passive"))
    )
    (net (code "74") (name "Net-(IC6A-6Q)") (class "Default")
      (node (ref "IC6") (pin "15") (pinfunction "6Q_15") (pintype "tri_state"))
      (node (ref "SV3") (pin "3") (pinfunction "3_3") (pintype "passive"))
    )
    (net (code "75") (name "Net-(IC6A-7Q)") (class "Default")
      (node (ref "IC6") (pin "16") (pinfunction "7Q_16") (pintype "tri_state"))
      (node (ref "SV3") (pin "5") (pinfunction "5_5") (pintype "passive"))
    )
    (net (code "76") (name "Net-(IC6A-8Q)") (class "Default")
      (node (ref "IC6") (pin "19") (pinfunction "8Q_19") (pintype "tri_state"))
      (node (ref "SV3") (pin "7") (pinfunction "7_7") (pintype "passive"))
    )
    (net (code "77") (name "Net-(IC7A-1Q)") (class "Default")
      (node (ref "IC7") (pin "2") (pinfunction "1Q_2") (pintype "tri_state"))
      (node (ref "SV3") (pin "10") (pinfunction "10_10") (pintype "passive"))
    )
    (net (code "78") (name "Net-(IC7A-2Q)") (class "Default")
      (node (ref "IC7") (pin "5") (pinfunction "2Q_5") (pintype "tri_state"))
      (node (ref "SV3") (pin "12") (pinfunction "12_12") (pintype "passive"))
    )
    (net (code "79") (name "Net-(IC7A-3Q)") (class "Default")
      (node (ref "IC7") (pin "6") (pinfunction "3Q_6") (pintype "tri_state"))
      (node (ref "SV3") (pin "14") (pinfunction "14_14") (pintype "passive"))
    )
    (net (code "80") (name "Net-(IC7A-4Q)") (class "Default")
      (node (ref "IC7") (pin "9") (pinfunction "4Q_9") (pintype "tri_state"))
      (node (ref "SV3") (pin "16") (pinfunction "16_16") (pintype "passive"))
    )
    (net (code "81") (name "Net-(IC7A-5Q)") (class "Default")
      (node (ref "IC7") (pin "12") (pinfunction "5Q_12") (pintype "tri_state"))
      (node (ref "SV3") (pin "9") (pinfunction "9_9") (pintype "passive"))
    )
    (net (code "82") (name "Net-(IC7A-6Q)") (class "Default")
      (node (ref "IC7") (pin "15") (pinfunction "6Q_15") (pintype "tri_state"))
      (node (ref "SV3") (pin "11") (pinfunction "11_11") (pintype "passive"))
    )
    (net (code "83") (name "Net-(IC7A-7Q)") (class "Default")
      (node (ref "IC7") (pin "16") (pinfunction "7Q_16") (pintype "tri_state"))
      (node (ref "SV3") (pin "13") (pinfunction "13_13") (pintype "passive"))
    )
    (net (code "84") (name "Net-(IC7A-8Q)") (class "Default")
      (node (ref "IC7") (pin "19") (pinfunction "8Q_19") (pintype "tri_state"))
      (node (ref "SV3") (pin "15") (pinfunction "15_15") (pintype "passive"))
    )
    (net (code "85") (name "Net-(IC8A-1Q)") (class "Default")
      (node (ref "IC8") (pin "2") (pinfunction "1Q_2") (pintype "tri_state"))
      (node (ref "SV4") (pin "2") (pinfunction "2_2") (pintype "passive"))
    )
    (net (code "86") (name "Net-(IC8A-2Q)") (class "Default")
      (node (ref "IC8") (pin "5") (pinfunction "2Q_5") (pintype "tri_state"))
      (node (ref "SV4") (pin "4") (pinfunction "4_4") (pintype "passive"))
    )
    (net (code "87") (name "Net-(IC8A-3Q)") (class "Default")
      (node (ref "IC8") (pin "6") (pinfunction "3Q_6") (pintype "tri_state"))
      (node (ref "SV4") (pin "6") (pinfunction "6_6") (pintype "passive"))
    )
    (net (code "88") (name "Net-(IC8A-4Q)") (class "Default")
      (node (ref "IC8") (pin "9") (pinfunction "4Q_9") (pintype "tri_state"))
      (node (ref "SV4") (pin "8") (pinfunction "8_8") (pintype "passive"))
    )
    (net (code "89") (name "Net-(IC8A-5Q)") (class "Default")
      (node (ref "IC8") (pin "12") (pinfunction "5Q_12") (pintype "tri_state"))
      (node (ref "SV4") (pin "1") (pinfunction "1_1") (pintype "passive"))
    )
    (net (code "90") (name "Net-(IC8A-6Q)") (class "Default")
      (node (ref "IC8") (pin "15") (pinfunction "6Q_15") (pintype "tri_state"))
      (node (ref "SV4") (pin "3") (pinfunction "3_3") (pintype "passive"))
    )
    (net (code "91") (name "Net-(IC8A-7Q)") (class "Default")
      (node (ref "IC8") (pin "16") (pinfunction "7Q_16") (pintype "tri_state"))
      (node (ref "SV4") (pin "5") (pinfunction "5_5") (pintype "passive"))
    )
    (net (code "92") (name "Net-(IC8A-8Q)") (class "Default")
      (node (ref "IC8") (pin "19") (pinfunction "8Q_19") (pintype "tri_state"))
      (node (ref "SV4") (pin "7") (pinfunction "7_7") (pintype "passive"))
    )
    (net (code "93") (name "Net-(IC9A-1D)") (class "Default")
      (node (ref "IC9") (pin "3") (pinfunction "1D_3") (pintype "input"))
      (node (ref "SV2") (pin "10") (pinfunction "10_10") (pintype "passive"))
    )
    (net (code "94") (name "Net-(IC9A-2D)") (class "Default")
      (node (ref "IC9") (pin "4") (pinfunction "2D_4") (pintype "input"))
      (node (ref "SV2") (pin "12") (pinfunction "12_12") (pintype "passive"))
    )
    (net (code "95") (name "Net-(IC9A-3D)") (class "Default")
      (node (ref "IC9") (pin "7") (pinfunction "3D_7") (pintype "input"))
      (node (ref "SV2") (pin "14") (pinfunction "14_14") (pintype "passive"))
    )
    (net (code "96") (name "Net-(IC9A-4D)") (class "Default")
      (node (ref "IC9") (pin "8") (pinfunction "4D_8") (pintype "input"))
      (node (ref "SV2") (pin "16") (pinfunction "16_16") (pintype "passive"))
    )
    (net (code "97") (name "Net-(IC9A-5D)") (class "Default")
      (node (ref "IC9") (pin "13") (pinfunction "5D_13") (pintype "input"))
      (node (ref "SV2") (pin "9") (pinfunction "9_9") (pintype "passive"))
    )
    (net (code "98") (name "Net-(IC9A-6D)") (class "Default")
      (node (ref "IC9") (pin "14") (pinfunction "6D_14") (pintype "input"))
      (node (ref "SV2") (pin "11") (pinfunction "11_11") (pintype "passive"))
    )
    (net (code "99") (name "Net-(IC9A-7D)") (class "Default")
      (node (ref "IC9") (pin "17") (pinfunction "7D_17") (pintype "input"))
      (node (ref "SV2") (pin "13") (pinfunction "13_13") (pintype "passive"))
    )
    (net (code "100") (name "Net-(IC9A-8D)") (class "Default")
      (node (ref "IC9") (pin "18") (pinfunction "8D_18") (pintype "input"))
      (node (ref "SV2") (pin "15") (pinfunction "15_15") (pintype "passive"))
    )
    (net (code "101") (name "Net-(IC10A-1Q)") (class "Default")
      (node (ref "IC10") (pin "2") (pinfunction "1Q_2") (pintype "tri_state"))
      (node (ref "SV4") (pin "10") (pinfunction "10_10") (pintype "passive"))
    )
    (net (code "102") (name "Net-(IC10A-2Q)") (class "Default")
      (node (ref "IC10") (pin "5") (pinfunction "2Q_5") (pintype "tri_state"))
      (node (ref "SV4") (pin "12") (pinfunction "12_12") (pintype "passive"))
    )
    (net (code "103") (name "Net-(IC10A-3Q)") (class "Default")
      (node (ref "IC10") (pin "6") (pinfunction "3Q_6") (pintype "tri_state"))
      (node (ref "SV4") (pin "14") (pinfunction "14_14") (pintype "passive"))
    )
    (net (code "104") (name "Net-(IC10A-4Q)") (class "Default")
      (node (ref "IC10") (pin "9") (pinfunction "4Q_9") (pintype "tri_state"))
      (node (ref "SV4") (pin "16") (pinfunction "16_16") (pintype "passive"))
    )
    (net (code "105") (name "Net-(IC10A-5Q)") (class "Default")
      (node (ref "IC10") (pin "12") (pinfunction "5Q_12") (pintype "tri_state"))
      (node (ref "SV4") (pin "9") (pinfunction "9_9") (pintype "passive"))
    )
    (net (code "106") (name "Net-(IC10A-6Q)") (class "Default")
      (node (ref "IC10") (pin "15") (pinfunction "6Q_15") (pintype "tri_state"))
      (node (ref "SV4") (pin "11") (pinfunction "11_11") (pintype "passive"))
    )
    (net (code "107") (name "Net-(IC10A-7Q)") (class "Default")
      (node (ref "IC10") (pin "16") (pinfunction "7Q_16") (pintype "tri_state"))
      (node (ref "SV4") (pin "13") (pinfunction "13_13") (pintype "passive"))
    )
    (net (code "108") (name "Net-(IC10A-8Q)") (class "Default")
      (node (ref "IC10") (pin "19") (pinfunction "8Q_19") (pintype "tri_state"))
      (node (ref "SV4") (pin "15") (pinfunction "15_15") (pintype "passive"))
    )
    (net (code "109") (name "Net-(IC11A-1Q)") (class "Default")
      (node (ref "IC11") (pin "2") (pinfunction "1Q_2") (pintype "tri_state"))
      (node (ref "SV6") (pin "2") (pinfunction "2_2") (pintype "passive"))
    )
    (net (code "110") (name "Net-(IC11A-2Q)") (class "Default")
      (node (ref "IC11") (pin "5") (pinfunction "2Q_5") (pintype "tri_state"))
      (node (ref "SV6") (pin "4") (pinfunction "4_4") (pintype "passive"))
    )
    (net (code "111") (name "Net-(IC11A-3Q)") (class "Default")
      (node (ref "IC11") (pin "6") (pinfunction "3Q_6") (pintype "tri_state"))
      (node (ref "SV6") (pin "6") (pinfunction "6_6") (pintype "passive"))
    )
    (net (code "112") (name "Net-(IC11A-4Q)") (class "Default")
      (node (ref "IC11") (pin "9") (pinfunction "4Q_9") (pintype "tri_state"))
      (node (ref "SV6") (pin "8") (pinfunction "8_8") (pintype "passive"))
    )
    (net (code "113") (name "Net-(IC11A-5Q)") (class "Default")
      (node (ref "IC11") (pin "12") (pinfunction "5Q_12") (pintype "tri_state"))
      (node (ref "SV6") (pin "1") (pinfunction "1_1") (pintype "passive"))
    )
    (net (code "114") (name "Net-(IC11A-6Q)") (class "Default")
      (node (ref "IC11") (pin "15") (pinfunction "6Q_15") (pintype "tri_state"))
      (node (ref "SV6") (pin "3") (pinfunction "3_3") (pintype "passive"))
    )
    (net (code "115") (name "Net-(IC11A-7Q)") (class "Default")
      (node (ref "IC11") (pin "16") (pinfunction "7Q_16") (pintype "tri_state"))
      (node (ref "SV6") (pin "5") (pinfunction "5_5") (pintype "passive"))
    )
    (net (code "116") (name "Net-(IC11A-8Q)") (class "Default")
      (node (ref "IC11") (pin "19") (pinfunction "8Q_19") (pintype "tri_state"))
      (node (ref "SV6") (pin "7") (pinfunction "7_7") (pintype "passive"))
    )
    (net (code "117") (name "Net-(IC12A-1Q)") (class "Default")
      (node (ref "IC12") (pin "2") (pinfunction "1Q_2") (pintype "tri_state"))
      (node (ref "SV6") (pin "10") (pinfunction "10_10") (pintype "passive"))
    )
    (net (code "118") (name "Net-(IC12A-2Q)") (class "Default")
      (node (ref "IC12") (pin "5") (pinfunction "2Q_5") (pintype "tri_state"))
      (node (ref "SV6") (pin "12") (pinfunction "12_12") (pintype "passive"))
    )
    (net (code "119") (name "Net-(IC12A-3Q)") (class "Default")
      (node (ref "IC12") (pin "6") (pinfunction "3Q_6") (pintype "tri_state"))
      (node (ref "SV6") (pin "14") (pinfunction "14_14") (pintype "passive"))
    )
    (net (code "120") (name "Net-(IC12A-4Q)") (class "Default")
      (node (ref "IC12") (pin "9") (pinfunction "4Q_9") (pintype "tri_state"))
      (node (ref "SV6") (pin "16") (pinfunction "16_16") (pintype "passive"))
    )
    (net (code "121") (name "Net-(IC12A-5Q)") (class "Default")
      (node (ref "IC12") (pin "12") (pinfunction "5Q_12") (pintype "tri_state"))
      (node (ref "SV6") (pin "9") (pinfunction "9_9") (pintype "passive"))
    )
    (net (code "122") (name "Net-(IC12A-6Q)") (class "Default")
      (node (ref "IC12") (pin "15") (pinfunction "6Q_15") (pintype "tri_state"))
      (node (ref "SV6") (pin "11") (pinfunction "11_11") (pintype "passive"))
    )
    (net (code "123") (name "Net-(IC12A-7Q)") (class "Default")
      (node (ref "IC12") (pin "16") (pinfunction "7Q_16") (pintype "tri_state"))
      (node (ref "SV6") (pin "13") (pinfunction "13_13") (pintype "passive"))
    )
    (net (code "124") (name "Net-(IC12A-8Q)") (class "Default")
      (node (ref "IC12") (pin "19") (pinfunction "8Q_19") (pintype "tri_state"))
      (node (ref "SV6") (pin "15") (pinfunction "15_15") (pintype "passive"))
    )
    (net (code "125") (name "Net-(IC13A-1Q)") (class "Default")
      (node (ref "IC13") (pin "2") (pinfunction "1Q_2") (pintype "tri_state"))
      (node (ref "SV7") (pin "2") (pinfunction "2_2") (pintype "passive"))
    )
    (net (code "126") (name "Net-(IC13A-2Q)") (class "Default")
      (node (ref "IC13") (pin "5") (pinfunction "2Q_5") (pintype "tri_state"))
      (node (ref "SV7") (pin "4") (pinfunction "4_4") (pintype "passive"))
    )
    (net (code "127") (name "Net-(IC13A-3Q)") (class "Default")
      (node (ref "IC13") (pin "6") (pinfunction "3Q_6") (pintype "tri_state"))
      (node (ref "SV7") (pin "6") (pinfunction "6_6") (pintype "passive"))
    )
    (net (code "128") (name "Net-(IC13A-4Q)") (class "Default")
      (node (ref "IC13") (pin "9") (pinfunction "4Q_9") (pintype "tri_state"))
      (node (ref "SV7") (pin "8") (pinfunction "8_8") (pintype "passive"))
    )
    (net (code "129") (name "Net-(IC13A-5Q)") (class "Default")
      (node (ref "IC13") (pin "12") (pinfunction "5Q_12") (pintype "tri_state"))
      (node (ref "SV7") (pin "1") (pinfunction "1_1") (pintype "passive"))
    )
    (net (code "130") (name "Net-(IC13A-6Q)") (class "Default")
      (node (ref "IC13") (pin "15") (pinfunction "6Q_15") (pintype "tri_state"))
      (node (ref "SV7") (pin "3") (pinfunction "3_3") (pintype "passive"))
    )
    (net (code "131") (name "Net-(IC13A-7Q)") (class "Default")
      (node (ref "IC13") (pin "16") (pinfunction "7Q_16") (pintype "tri_state"))
      (node (ref "SV7") (pin "5") (pinfunction "5_5") (pintype "passive"))
    )
    (net (code "132") (name "Net-(IC13A-8Q)") (class "Default")
      (node (ref "IC13") (pin "19") (pinfunction "8Q_19") (pintype "tri_state"))
      (node (ref "SV7") (pin "7") (pinfunction "7_7") (pintype "passive"))
    )
    (net (code "133") (name "Net-(IC14A-1Q)") (class "Default")
      (node (ref "IC14") (pin "2") (pinfunction "1Q_2") (pintype "tri_state"))
      (node (ref "SV7") (pin "10") (pinfunction "10_10") (pintype "passive"))
    )
    (net (code "134") (name "Net-(IC14A-2Q)") (class "Default")
      (node (ref "IC14") (pin "5") (pinfunction "2Q_5") (pintype "tri_state"))
      (node (ref "SV7") (pin "12") (pinfunction "12_12") (pintype "passive"))
    )
    (net (code "135") (name "Net-(IC14A-3Q)") (class "Default")
      (node (ref "IC14") (pin "6") (pinfunction "3Q_6") (pintype "tri_state"))
      (node (ref "SV7") (pin "14") (pinfunction "14_14") (pintype "passive"))
    )
    (net (code "136") (name "Net-(IC14A-4Q)") (class "Default")
      (node (ref "IC14") (pin "9") (pinfunction "4Q_9") (pintype "tri_state"))
      (node (ref "SV7") (pin "16") (pinfunction "16_16") (pintype "passive"))
    )
    (net (code "137") (name "Net-(IC14A-5Q)") (class "Default")
      (node (ref "IC14") (pin "12") (pinfunction "5Q_12") (pintype "tri_state"))
      (node (ref "SV7") (pin "9") (pinfunction "9_9") (pintype "passive"))
    )
    (net (code "138") (name "Net-(IC14A-6Q)") (class "Default")
      (node (ref "IC14") (pin "15") (pinfunction "6Q_15") (pintype "tri_state"))
      (node (ref "SV7") (pin "11") (pinfunction "11_11") (pintype "passive"))
    )
    (net (code "139") (name "Net-(IC14A-7Q)") (class "Default")
      (node (ref "IC14") (pin "16") (pinfunction "7Q_16") (pintype "tri_state"))
      (node (ref "SV7") (pin "13") (pinfunction "13_13") (pintype "passive"))
    )
    (net (code "140") (name "Net-(IC14A-8Q)") (class "Default")
      (node (ref "IC14") (pin "19") (pinfunction "8Q_19") (pintype "tri_state"))
      (node (ref "SV7") (pin "15") (pinfunction "15_15") (pintype "passive"))
    )
    (net (code "141") (name "Net-(IC15A-1D)") (class "Default")
      (node (ref "IC15") (pin "3") (pinfunction "1D_3") (pintype "input"))
      (node (ref "SV5") (pin "2") (pinfunction "2_2") (pintype "passive"))
    )
    (net (code "142") (name "Net-(IC15A-2D)") (class "Default")
      (node (ref "IC15") (pin "4") (pinfunction "2D_4") (pintype "input"))
      (node (ref "SV5") (pin "4") (pinfunction "4_4") (pintype "passive"))
    )
    (net (code "143") (name "Net-(IC15A-3D)") (class "Default")
      (node (ref "IC15") (pin "7") (pinfunction "3D_7") (pintype "input"))
      (node (ref "SV5") (pin "6") (pinfunction "6_6") (pintype "passive"))
    )
    (net (code "144") (name "Net-(IC15A-4D)") (class "Default")
      (node (ref "IC15") (pin "8") (pinfunction "4D_8") (pintype "input"))
      (node (ref "SV5") (pin "8") (pinfunction "8_8") (pintype "passive"))
    )
    (net (code "145") (name "Net-(IC15A-5D)") (class "Default")
      (node (ref "IC15") (pin "13") (pinfunction "5D_13") (pintype "input"))
      (node (ref "SV5") (pin "1") (pinfunction "1_1") (pintype "passive"))
    )
    (net (code "146") (name "Net-(IC15A-6D)") (class "Default")
      (node (ref "IC15") (pin "14") (pinfunction "6D_14") (pintype "input"))
      (node (ref "SV5") (pin "3") (pinfunction "3_3") (pintype "passive"))
    )
    (net (code "147") (name "Net-(IC15A-7D)") (class "Default")
      (node (ref "IC15") (pin "17") (pinfunction "7D_17") (pintype "input"))
      (node (ref "SV5") (pin "5") (pinfunction "5_5") (pintype "passive"))
    )
    (net (code "148") (name "Net-(IC15A-8D)") (class "Default")
      (node (ref "IC15") (pin "18") (pinfunction "8D_18") (pintype "input"))
      (node (ref "SV5") (pin "7") (pinfunction "7_7") (pintype "passive"))
    )
    (net (code "149") (name "Net-(IC16A-1D)") (class "Default")
      (node (ref "IC16") (pin "3") (pinfunction "1D_3") (pintype "input"))
      (node (ref "SV5") (pin "10") (pinfunction "10_10") (pintype "passive"))
    )
    (net (code "150") (name "Net-(IC16A-2D)") (class "Default")
      (node (ref "IC16") (pin "4") (pinfunction "2D_4") (pintype "input"))
      (node (ref "SV5") (pin "12") (pinfunction "12_12") (pintype "passive"))
    )
    (net (code "151") (name "Net-(IC16A-3D)") (class "Default")
      (node (ref "IC16") (pin "7") (pinfunction "3D_7") (pintype "input"))
      (node (ref "SV5") (pin "14") (pinfunction "14_14") (pintype "passive"))
    )
    (net (code "152") (name "Net-(IC16A-4D)") (class "Default")
      (node (ref "IC16") (pin "8") (pinfunction "4D_8") (pintype "input"))
      (node (ref "SV5") (pin "16") (pinfunction "16_16") (pintype "passive"))
    )
    (net (code "153") (name "Net-(IC16A-5D)") (class "Default")
      (node (ref "IC16") (pin "13") (pinfunction "5D_13") (pintype "input"))
      (node (ref "SV5") (pin "9") (pinfunction "9_9") (pintype "passive"))
    )
    (net (code "154") (name "Net-(IC16A-6D)") (class "Default")
      (node (ref "IC16") (pin "14") (pinfunction "6D_14") (pintype "input"))
      (node (ref "SV5") (pin "11") (pinfunction "11_11") (pintype "passive"))
    )
    (net (code "155") (name "Net-(IC16A-7D)") (class "Default")
      (node (ref "IC16") (pin "17") (pinfunction "7D_17") (pintype "input"))
      (node (ref "SV5") (pin "13") (pinfunction "13_13") (pintype "passive"))
    )
    (net (code "156") (name "Net-(IC16A-8D)") (class "Default")
      (node (ref "IC16") (pin "18") (pinfunction "8D_18") (pintype "input"))
      (node (ref "SV5") (pin "15") (pinfunction "15_15") (pintype "passive"))
    )
    (net (code "157") (name "Net-(IC17A-EXTAL)") (class "Default")
      (node (ref "C2") (pin "1") (pinfunction "1_1") (pintype "passive"))
      (node (ref "IC17") (pin "39") (pinfunction "EXTAL_39") (pintype "input"))
      (node (ref "Q1") (pin "1") (pinfunction "1_1") (pintype "passive"))
    )
    (net (code "158") (name "Net-(IC17A-XTAL)") (class "Default")
      (node (ref "C1") (pin "2") (pinfunction "2_2") (pintype "passive"))
      (node (ref "IC17") (pin "38") (pinfunction "XTAL_38") (pintype "input"))
      (node (ref "Q1") (pin "2") (pinfunction "2_2") (pintype "passive"))
    )
    (net (code "159") (name "Net-(IC18A-I0)") (class "Default")
      (node (ref "C3") (pin "1") (pinfunction "1_1") (pintype "passive"))
      (node (ref "IC18") (pin "1") (pinfunction "I0_1") (pintype "input"))
      (node (ref "R1") (pin "1") (pinfunction "1_1") (pintype "passive"))
    )
    (net (code "160") (name "Net-(IC18A-I1)") (class "Default")
      (node (ref "IC18") (pin "2") (pinfunction "I1_2") (pintype "input"))
      (node (ref "JP1") (pin "2") (pinfunction "2_2") (pintype "passive"))
      (node (ref "R2") (pin "1") (pinfunction "1_1") (pintype "passive"))
    )
    (net (code "161") (name "Net-(IC18A-O)") (class "Default")
      (node (ref "IC18") (pin "3") (pinfunction "O_3") (pintype "output"))
      (node (ref "IC18") (pin "4") (pinfunction "I0_4") (pintype "input"))
      (node (ref "IC18") (pin "5") (pinfunction "I1_5") (pintype "input"))
    )
    (net (code "162") (name "Net-(IC18C-O)") (class "Default")
      (node (ref "IC18") (pin "8") (pinfunction "O_8") (pintype "output"))
      (node (ref "IC28") (pin "4") (pinfunction "G2A_4") (pintype "input"))
    )
    (net (code "163") (name "Net-(IC18D-I0)") (class "Default")
      (node (ref "IC18") (pin "12") (pinfunction "I0_12") (pintype "input"))
      (node (ref "IC18") (pin "13") (pinfunction "I1_13") (pintype "input"))
      (node (ref "IC21") (pin "5") (pinfunction "RTS_5") (pintype "output"))
    )
    (net (code "164") (name "Net-(IC18D-O)") (class "Default")
      (node (ref "IC18") (pin "11") (pinfunction "O_11") (pintype "output"))
      (node (ref "LED1") (pin "K") (pinfunction "C_K") (pintype "passive"))
    )
    (net (code "165") (name "Net-(IC19A-G2B)") (class "Default")
      (node (ref "IC19") (pin "5") (pinfunction "G2B_5") (pintype "input"))
      (node (ref "IC28") (pin "15") (pinfunction "Y0_15") (pintype "output"))
    )
    (net (code "166") (name "Net-(IC20A-C1+)") (class "Default")
      (node (ref "C8") (pin "1") (pinfunction "1_1") (pintype "passive"))
      (node (ref "IC20") (pin "1") (pinfunction "C1+_1") (pintype "bidirectional"))
    )
    (net (code "167") (name "Net-(IC20A-C1-)") (class "Default")
      (node (ref "C8") (pin "2") (pinfunction "2_2") (pintype "passive"))
      (node (ref "IC20") (pin "3") (pinfunction "C1-_3") (pintype "bidirectional"))
    )
    (net (code "168") (name "Net-(IC20A-C2+)") (class "Default")
      (node (ref "C9") (pin "1") (pinfunction "1_1") (pintype "passive"))
      (node (ref "IC20") (pin "4") (pinfunction "C2+_4") (pintype "bidirectional"))
    )
    (net (code "169") (name "Net-(IC20A-C2-)") (class "Default")
      (node (ref "C9") (pin "2") (pinfunction "2_2") (pintype "passive"))
      (node (ref "IC20") (pin "5") (pinfunction "C2-_5") (pintype "bidirectional"))
    )
    (net (code "170") (name "Net-(IC20A-R2IN)") (class "Default")
      (node (ref "IC20") (pin "7") (pinfunction "T2OUT_7") (pintype "output"))
      (node (ref "IC20") (pin "8") (pinfunction "R2IN_8") (pintype "input"))
    )
    (net (code "171") (name "Net-(IC20A-V+)") (class "Default")
      (node (ref "C10") (pin "2") (pinfunction "2_2") (pintype "passive"))
      (node (ref "IC20") (pin "2") (pinfunction "V+_2") (pintype "bidirectional"))
    )
    (net (code "172") (name "Net-(IC20A-V-)") (class "Default")
      (node (ref "C11") (pin "1") (pinfunction "1_1") (pintype "passive"))
      (node (ref "IC20") (pin "6") (pinfunction "V-_6") (pintype "bidirectional"))
    )
    (net (code "173") (name "Net-(IC21A-CTS)") (class "Default")
      (node (ref "IC21") (pin "24") (pinfunction "CTS_24") (pintype "input"))
      (node (ref "JP2") (pin "1") (pinfunction "1_1") (pintype "passive"))
      (node (ref "R13") (pin "2") (pinfunction "2_2") (pintype "passive"))
    )
    (net (code "174") (name "Net-(IC21A-RXCLK)") (class "Default")
      (node (ref "IC21") (pin "3") (pinfunction "RXCLK_3") (pintype "input"))
      (node (ref "IC21") (pin "4") (pinfunction "TXCLK_4") (pintype "input"))
      (node (ref "IC27") (pin "5") (pinfunction "Q_5") (pintype "output"))
    )
    (net (code "175") (name "Net-(IC24A-CA1)") (class "Default")
      (node (ref "IC24") (pin "40") (pinfunction "CA1_40") (pintype "input"))
      (node (ref "IC27") (pin "9") (pinfunction "Q_9") (pintype "output"))
    )
    (net (code "176") (name "Net-(IC24A-CA2)") (class "Default")
      (node (ref "IC24") (pin "39") (pinfunction "CA2_39") (pintype "bidirectional"))
      (node (ref "IC25") (pin "1") (pinfunction "DIR_1") (pintype "input"))
    )
    (net (code "177") (name "Net-(IC24A-CB2)") (class "Default")
      (node (ref "IC24") (pin "19") (pinfunction "CB2_19") (pintype "bidirectional"))
      (node (ref "IC26") (pin "1") (pinfunction "DIR_1") (pintype "input"))
    )
    (net (code "178") (name "Net-(IC24A-PA0)") (class "Default")
      (node (ref "IC24") (pin "2") (pinfunction "PA0_2") (pintype "bidirectional"))
      (node (ref "IC25") (pin "2") (pinfunction "A1_2") (pintype "bidirectional"))
    )
    (net (code "179") (name "Net-(IC24A-PA1)") (class "Default")
      (node (ref "IC24") (pin "3") (pinfunction "PA1_3") (pintype "bidirectional"))
      (node (ref "IC25") (pin "3") (pinfunction "A2_3") (pintype "bidirectional"))
    )
    (net (code "180") (name "Net-(IC24A-PA2)") (class "Default")
      (node (ref "IC24") (pin "4") (pinfunction "PA2_4") (pintype "bidirectional"))
      (node (ref "IC25") (pin "4") (pinfunction "A3_4") (pintype "bidirectional"))
    )
    (net (code "181") (name "Net-(IC24A-PA3)") (class "Default")
      (node (ref "IC24") (pin "5") (pinfunction "PA3_5") (pintype "bidirectional"))
      (node (ref "IC25") (pin "5") (pinfunction "A4_5") (pintype "bidirectional"))
    )
    (net (code "182") (name "Net-(IC24A-PA4)") (class "Default")
      (node (ref "IC24") (pin "6") (pinfunction "PA4_6") (pintype "bidirectional"))
      (node (ref "IC25") (pin "6") (pinfunction "A5_6") (pintype "bidirectional"))
    )
    (net (code "183") (name "Net-(IC24A-PA5)") (class "Default")
      (node (ref "IC24") (pin "7") (pinfunction "PA5_7") (pintype "bidirectional"))
      (node (ref "IC25") (pin "7") (pinfunction "A6_7") (pintype "bidirectional"))
    )
    (net (code "184") (name "Net-(IC24A-PA6)") (class "Default")
      (node (ref "IC24") (pin "8") (pinfunction "PA6_8") (pintype "bidirectional"))
      (node (ref "IC25") (pin "8") (pinfunction "A7_8") (pintype "bidirectional"))
    )
    (net (code "185") (name "Net-(IC24A-PA7)") (class "Default")
      (node (ref "IC24") (pin "9") (pinfunction "PA7_9") (pintype "bidirectional"))
      (node (ref "IC25") (pin "9") (pinfunction "A8_9") (pintype "bidirectional"))
    )
    (net (code "186") (name "Net-(IC24A-PB0)") (class "Default")
      (node (ref "IC24") (pin "10") (pinfunction "PB0_10") (pintype "bidirectional"))
      (node (ref "IC26") (pin "2") (pinfunction "A1_2") (pintype "bidirectional"))
    )
    (net (code "187") (name "Net-(IC24A-PB1)") (class "Default")
      (node (ref "IC24") (pin "11") (pinfunction "PB1_11") (pintype "bidirectional"))
      (node (ref "IC26") (pin "3") (pinfunction "A2_3") (pintype "bidirectional"))
    )
    (net (code "188") (name "Net-(IC24A-PB2)") (class "Default")
      (node (ref "IC24") (pin "12") (pinfunction "PB2_12") (pintype "bidirectional"))
      (node (ref "IC26") (pin "4") (pinfunction "A3_4") (pintype "bidirectional"))
    )
    (net (code "189") (name "Net-(IC24A-PB3)") (class "Default")
      (node (ref "IC24") (pin "13") (pinfunction "PB3_13") (pintype "bidirectional"))
      (node (ref "IC26") (pin "5") (pinfunction "A4_5") (pintype "bidirectional"))
    )
    (net (code "190") (name "Net-(IC24A-PB4)") (class "Default")
      (node (ref "IC24") (pin "14") (pinfunction "PB4_14") (pintype "bidirectional"))
      (node (ref "IC26") (pin "6") (pinfunction "A5_6") (pintype "bidirectional"))
    )
    (net (code "191") (name "Net-(IC24A-PB5)") (class "Default")
      (node (ref "IC24") (pin "15") (pinfunction "PB5_15") (pintype "bidirectional"))
      (node (ref "IC26") (pin "7") (pinfunction "A6_7") (pintype "bidirectional"))
    )
    (net (code "192") (name "Net-(IC24A-PB6)") (class "Default")
      (node (ref "IC24") (pin "16") (pinfunction "PB6_16") (pintype "bidirectional"))
      (node (ref "IC26") (pin "8") (pinfunction "A7_8") (pintype "bidirectional"))
    )
    (net (code "193") (name "Net-(IC24A-PB7)") (class "Default")
      (node (ref "IC24") (pin "17") (pinfunction "PB7_17") (pintype "bidirectional"))
      (node (ref "IC26") (pin "9") (pinfunction "A8_9") (pintype "bidirectional"))
    )
    (net (code "194") (name "Net-(IC27A-CV)") (class "Default")
      (node (ref "C7") (pin "1") (pinfunction "1_1") (pintype "passive"))
      (node (ref "IC27") (pin "3") (pinfunction "CV_3") (pintype "input"))
    )
    (net (code "195") (name "Net-(IC27A-DIS)") (class "Default")
      (node (ref "IC27") (pin "1") (pinfunction "DIS_1") (pintype "input"))
      (node (ref "R10") (pin "2") (pinfunction "2_2") (pintype "passive"))
      (node (ref "R9") (pin "1") (pinfunction "1_1") (pintype "passive"))
    )
    (net (code "196") (name "Net-(IC27A-THR)") (class "Default")
      (node (ref "C6") (pin "1") (pinfunction "1_1") (pintype "passive"))
      (node (ref "IC27") (pin "2") (pinfunction "THR_2") (pintype "input"))
      (node (ref "IC27") (pin "6") (pinfunction "TR_6") (pintype "input"))
      (node (ref "R11") (pin "A") (pinfunction "A_A") (pintype "passive"))
    )
    (net (code "197") (name "Net-(IC27B-CV)") (class "Default")
      (node (ref "C5") (pin "1") (pinfunction "1_1") (pintype "passive"))
      (node (ref "IC27") (pin "11") (pinfunction "CV_11") (pintype "input"))
    )
    (net (code "198") (name "Net-(IC27B-DIS)") (class "Default")
      (node (ref "IC27") (pin "13") (pinfunction "DIS_13") (pintype "input"))
      (node (ref "R3") (pin "1") (pinfunction "1_1") (pintype "passive"))
      (node (ref "R4") (pin "2") (pinfunction "2_2") (pintype "passive"))
    )
    (net (code "199") (name "Net-(IC27B-THR)") (class "Default")
      (node (ref "C4") (pin "1") (pinfunction "1_1") (pintype "passive"))
      (node (ref "IC27") (pin "12") (pinfunction "THR_12") (pintype "input"))
      (node (ref "IC27") (pin "8") (pinfunction "TR_8") (pintype "input"))
      (node (ref "R4") (pin "1") (pinfunction "1_1") (pintype "passive"))
    )
    (net (code "200") (name "Net-(LED1-PadA)") (class "Default")
      (node (ref "LED1") (pin "A") (pinfunction "A_A") (pintype "passive"))
      (node (ref "R12") (pin "1") (pinfunction "1_1") (pintype "passive"))
    )
    (net (code "201") (name "Net-(R10-Pad1)") (class "Default")
      (node (ref "R10") (pin "1") (pinfunction "1_1") (pintype "passive"))
      (node (ref "R11") (pin "E") (pinfunction "E_E") (pintype "passive"))
    )
    (net (code "202") (name "Net-(X1-Pad4)") (class "Default")
      (node (ref "X1") (pin "4") (pinfunction "4_4") (pintype "passive"))
      (node (ref "X1") (pin "6") (pinfunction "6_6") (pintype "passive"))
    )
    (net (code "203") (name "Net-(X1-Pad5)") (class "Default")
      (node (ref "X1") (pin "5") (pinfunction "5_5") (pintype "passive"))
      (node (ref "X1") (pin "G1") (pinfunction "G1_G1") (pintype "passive"))
      (node (ref "X1") (pin "G2") (pinfunction "G2_G2") (pintype "passive"))
    )
    (net (code "204") (name "Net-(X1-Pad7)") (class "Default")
      (node (ref "X1") (pin "7") (pinfunction "7_7") (pintype "passive"))
      (node (ref "X1") (pin "8") (pinfunction "8_8") (pintype "passive"))
    )
    (net (code "205") (name "OUT00") (class "Default")
      (node (ref "IC1") (pin "1") (pinfunction "0_1") (pintype "output"))
      (node (ref "IC6") (pin "11") (pinfunction "CLK_11") (pintype "input"))
    )
    (net (code "206") (name "OUT01") (class "Default")
      (node (ref "IC1") (pin "2") (pinfunction "1_2") (pintype "output"))
      (node (ref "IC7") (pin "11") (pinfunction "CLK_11") (pintype "input"))
    )
    (net (code "207") (name "OUT02") (class "Default")
      (node (ref "IC1") (pin "3") (pinfunction "2_3") (pintype "output"))
      (node (ref "IC8") (pin "11") (pinfunction "CLK_11") (pintype "input"))
    )
    (net (code "208") (name "OUT03") (class "Default")
      (node (ref "IC1") (pin "4") (pinfunction "3_4") (pintype "output"))
      (node (ref "IC10") (pin "11") (pinfunction "CLK_11") (pintype "input"))
    )
    (net (code "209") (name "OUT04") (class "Default")
      (node (ref "IC1") (pin "5") (pinfunction "4_5") (pintype "output"))
      (node (ref "IC11") (pin "11") (pinfunction "CLK_11") (pintype "input"))
    )
    (net (code "210") (name "OUT05") (class "Default")
      (node (ref "IC1") (pin "6") (pinfunction "5_6") (pintype "output"))
      (node (ref "IC12") (pin "11") (pinfunction "CLK_11") (pintype "input"))
    )
    (net (code "211") (name "OUT06") (class "Default")
      (node (ref "IC1") (pin "7") (pinfunction "6_7") (pintype "output"))
      (node (ref "IC13") (pin "11") (pinfunction "CLK_11") (pintype "input"))
    )
    (net (code "212") (name "OUT07") (class "Default")
      (node (ref "IC1") (pin "8") (pinfunction "7_8") (pintype "output"))
      (node (ref "IC14") (pin "11") (pinfunction "CLK_11") (pintype "input"))
    )
    (net (code "213") (name "OUT08") (class "Default")
      (node (ref "IC1") (pin "9") (pinfunction "8_9") (pintype "output"))
    )
    (net (code "214") (name "OUT09") (class "Default")
      (node (ref "IC1") (pin "10") (pinfunction "9_10") (pintype "output"))
    )
    (net (code "215") (name "OUT10") (class "Default")
      (node (ref "IC1") (pin "11") (pinfunction "10_11") (pintype "output"))
    )
    (net (code "216") (name "OUT11") (class "Default")
      (node (ref "IC1") (pin "13") (pinfunction "11_13") (pintype "output"))
    )
    (net (code "217") (name "OUT12") (class "Default")
      (node (ref "IC1") (pin "14") (pinfunction "12_14") (pintype "output"))
    )
    (net (code "218") (name "OUT13") (class "Default")
      (node (ref "IC1") (pin "15") (pinfunction "13_15") (pintype "output"))
    )
    (net (code "219") (name "OUT14") (class "Default")
      (node (ref "IC1") (pin "16") (pinfunction "14_16") (pintype "output"))
    )
    (net (code "220") (name "OUT15") (class "Default")
      (node (ref "IC1") (pin "17") (pinfunction "15_17") (pintype "output"))
    )
    (net (code "221") (name "PIA-A0") (class "Default")
      (node (ref "IC10") (pin "3") (pinfunction "1D_3") (pintype "input"))
      (node (ref "IC11") (pin "3") (pinfunction "1D_3") (pintype "input"))
      (node (ref "IC12") (pin "3") (pinfunction "1D_3") (pintype "input"))
      (node (ref "IC13") (pin "3") (pinfunction "1D_3") (pintype "input"))
      (node (ref "IC14") (pin "3") (pinfunction "1D_3") (pintype "input"))
      (node (ref "IC15") (pin "2") (pinfunction "1Q_2") (pintype "tri_state"))
      (node (ref "IC16") (pin "2") (pinfunction "1Q_2") (pintype "tri_state"))
      (node (ref "IC2") (pin "2") (pinfunction "1Q_2") (pintype "tri_state"))
      (node (ref "IC25") (pin "18") (pinfunction "B1_18") (pintype "bidirectional"))
      (node (ref "IC3") (pin "2") (pinfunction "1Q_2") (pintype "tri_state"))
      (node (ref "IC4") (pin "2") (pinfunction "1Q_2") (pintype "tri_state"))
      (node (ref "IC6") (pin "3") (pinfunction "1D_3") (pintype "input"))
      (node (ref "IC7") (pin "3") (pinfunction "1D_3") (pintype "input"))
      (node (ref "IC8") (pin "3") (pinfunction "1D_3") (pintype "input"))
      (node (ref "IC9") (pin "2") (pinfunction "1Q_2") (pintype "tri_state"))
      (node (ref "SV9") (pin "1") (pinfunction "1_1") (pintype "passive"))
    )
    (net (code "222") (name "PIA-A1") (class "Default")
      (node (ref "IC10") (pin "4") (pinfunction "2D_4") (pintype "input"))
      (node (ref "IC11") (pin "4") (pinfunction "2D_4") (pintype "input"))
      (node (ref "IC12") (pin "4") (pinfunction "2D_4") (pintype "input"))
      (node (ref "IC13") (pin "4") (pinfunction "2D_4") (pintype "input"))
      (node (ref "IC14") (pin "4") (pinfunction "2D_4") (pintype "input"))
      (node (ref "IC15") (pin "5") (pinfunction "2Q_5") (pintype "tri_state"))
      (node (ref "IC16") (pin "5") (pinfunction "2Q_5") (pintype "tri_state"))
      (node (ref "IC2") (pin "5") (pinfunction "2Q_5") (pintype "tri_state"))
      (node (ref "IC25") (pin "17") (pinfunction "B2_17") (pintype "bidirectional"))
      (node (ref "IC3") (pin "5") (pinfunction "2Q_5") (pintype "tri_state"))
      (node (ref "IC4") (pin "5") (pinfunction "2Q_5") (pintype "tri_state"))
      (node (ref "IC6") (pin "4") (pinfunction "2D_4") (pintype "input"))
      (node (ref "IC7") (pin "4") (pinfunction "2D_4") (pintype "input"))
      (node (ref "IC8") (pin "4") (pinfunction "2D_4") (pintype "input"))
      (node (ref "IC9") (pin "5") (pinfunction "2Q_5") (pintype "tri_state"))
      (node (ref "SV9") (pin "3") (pinfunction "3_3") (pintype "passive"))
    )
    (net (code "223") (name "PIA-A2") (class "Default")
      (node (ref "IC10") (pin "7") (pinfunction "3D_7") (pintype "input"))
      (node (ref "IC11") (pin "7") (pinfunction "3D_7") (pintype "input"))
      (node (ref "IC12") (pin "7") (pinfunction "3D_7") (pintype "input"))
      (node (ref "IC13") (pin "7") (pinfunction "3D_7") (pintype "input"))
      (node (ref "IC14") (pin "7") (pinfunction "3D_7") (pintype "input"))
      (node (ref "IC15") (pin "6") (pinfunction "3Q_6") (pintype "tri_state"))
      (node (ref "IC16") (pin "6") (pinfunction "3Q_6") (pintype "tri_state"))
      (node (ref "IC2") (pin "6") (pinfunction "3Q_6") (pintype "tri_state"))
      (node (ref "IC25") (pin "16") (pinfunction "B3_16") (pintype "bidirectional"))
      (node (ref "IC3") (pin "6") (pinfunction "3Q_6") (pintype "tri_state"))
      (node (ref "IC4") (pin "6") (pinfunction "3Q_6") (pintype "tri_state"))
      (node (ref "IC6") (pin "7") (pinfunction "3D_7") (pintype "input"))
      (node (ref "IC7") (pin "7") (pinfunction "3D_7") (pintype "input"))
      (node (ref "IC8") (pin "7") (pinfunction "3D_7") (pintype "input"))
      (node (ref "IC9") (pin "6") (pinfunction "3Q_6") (pintype "tri_state"))
      (node (ref "SV9") (pin "5") (pinfunction "5_5") (pintype "passive"))
    )
    (net (code "224") (name "PIA-A3") (class "Default")
      (node (ref "IC10") (pin "8") (pinfunction "4D_8") (pintype "input"))
      (node (ref "IC11") (pin "8") (pinfunction "4D_8") (pintype "input"))
      (node (ref "IC12") (pin "8") (pinfunction "4D_8") (pintype "input"))
      (node (ref "IC13") (pin "8") (pinfunction "4D_8") (pintype "input"))
      (node (ref "IC14") (pin "8") (pinfunction "4D_8") (pintype "input"))
      (node (ref "IC15") (pin "9") (pinfunction "4Q_9") (pintype "tri_state"))
      (node (ref "IC16") (pin "9") (pinfunction "4Q_9") (pintype "tri_state"))
      (node (ref "IC2") (pin "9") (pinfunction "4Q_9") (pintype "tri_state"))
      (node (ref "IC25") (pin "15") (pinfunction "B4_15") (pintype "bidirectional"))
      (node (ref "IC3") (pin "9") (pinfunction "4Q_9") (pintype "tri_state"))
      (node (ref "IC4") (pin "9") (pinfunction "4Q_9") (pintype "tri_state"))
      (node (ref "IC6") (pin "8") (pinfunction "4D_8") (pintype "input"))
      (node (ref "IC7") (pin "8") (pinfunction "4D_8") (pintype "input"))
      (node (ref "IC8") (pin "8") (pinfunction "4D_8") (pintype "input"))
      (node (ref "IC9") (pin "9") (pinfunction "4Q_9") (pintype "tri_state"))
      (node (ref "SV9") (pin "7") (pinfunction "7_7") (pintype "passive"))
    )
    (net (code "225") (name "PIA-A4") (class "Default")
      (node (ref "IC10") (pin "13") (pinfunction "5D_13") (pintype "input"))
      (node (ref "IC11") (pin "13") (pinfunction "5D_13") (pintype "input"))
      (node (ref "IC12") (pin "13") (pinfunction "5D_13") (pintype "input"))
      (node (ref "IC13") (pin "13") (pinfunction "5D_13") (pintype "input"))
      (node (ref "IC14") (pin "13") (pinfunction "5D_13") (pintype "input"))
      (node (ref "IC15") (pin "12") (pinfunction "5Q_12") (pintype "tri_state"))
      (node (ref "IC16") (pin "12") (pinfunction "5Q_12") (pintype "tri_state"))
      (node (ref "IC2") (pin "12") (pinfunction "5Q_12") (pintype "tri_state"))
      (node (ref "IC25") (pin "14") (pinfunction "B5_14") (pintype "bidirectional"))
      (node (ref "IC3") (pin "12") (pinfunction "5Q_12") (pintype "tri_state"))
      (node (ref "IC4") (pin "12") (pinfunction "5Q_12") (pintype "tri_state"))
      (node (ref "IC6") (pin "13") (pinfunction "5D_13") (pintype "input"))
      (node (ref "IC7") (pin "13") (pinfunction "5D_13") (pintype "input"))
      (node (ref "IC8") (pin "13") (pinfunction "5D_13") (pintype "input"))
      (node (ref "IC9") (pin "12") (pinfunction "5Q_12") (pintype "tri_state"))
      (node (ref "SV9") (pin "9") (pinfunction "9_9") (pintype "passive"))
    )
    (net (code "226") (name "PIA-A5") (class "Default")
      (node (ref "IC10") (pin "14") (pinfunction "6D_14") (pintype "input"))
      (node (ref "IC11") (pin "14") (pinfunction "6D_14") (pintype "input"))
      (node (ref "IC12") (pin "14") (pinfunction "6D_14") (pintype "input"))
      (node (ref "IC13") (pin "14") (pinfunction "6D_14") (pintype "input"))
      (node (ref "IC14") (pin "14") (pinfunction "6D_14") (pintype "input"))
      (node (ref "IC15") (pin "15") (pinfunction "6Q_15") (pintype "tri_state"))
      (node (ref "IC16") (pin "15") (pinfunction "6Q_15") (pintype "tri_state"))
      (node (ref "IC2") (pin "15") (pinfunction "6Q_15") (pintype "tri_state"))
      (node (ref "IC25") (pin "13") (pinfunction "B6_13") (pintype "bidirectional"))
      (node (ref "IC3") (pin "15") (pinfunction "6Q_15") (pintype "tri_state"))
      (node (ref "IC4") (pin "15") (pinfunction "6Q_15") (pintype "tri_state"))
      (node (ref "IC6") (pin "14") (pinfunction "6D_14") (pintype "input"))
      (node (ref "IC7") (pin "14") (pinfunction "6D_14") (pintype "input"))
      (node (ref "IC8") (pin "14") (pinfunction "6D_14") (pintype "input"))
      (node (ref "IC9") (pin "15") (pinfunction "6Q_15") (pintype "tri_state"))
      (node (ref "SV9") (pin "11") (pinfunction "11_11") (pintype "passive"))
    )
    (net (code "227") (name "PIA-A6") (class "Default")
      (node (ref "IC10") (pin "17") (pinfunction "7D_17") (pintype "input"))
      (node (ref "IC11") (pin "17") (pinfunction "7D_17") (pintype "input"))
      (node (ref "IC12") (pin "17") (pinfunction "7D_17") (pintype "input"))
      (node (ref "IC13") (pin "17") (pinfunction "7D_17") (pintype "input"))
      (node (ref "IC14") (pin "17") (pinfunction "7D_17") (pintype "input"))
      (node (ref "IC15") (pin "16") (pinfunction "7Q_16") (pintype "tri_state"))
      (node (ref "IC16") (pin "16") (pinfunction "7Q_16") (pintype "tri_state"))
      (node (ref "IC2") (pin "16") (pinfunction "7Q_16") (pintype "tri_state"))
      (node (ref "IC25") (pin "12") (pinfunction "B7_12") (pintype "bidirectional"))
      (node (ref "IC3") (pin "16") (pinfunction "7Q_16") (pintype "tri_state"))
      (node (ref "IC4") (pin "16") (pinfunction "7Q_16") (pintype "tri_state"))
      (node (ref "IC6") (pin "17") (pinfunction "7D_17") (pintype "input"))
      (node (ref "IC7") (pin "17") (pinfunction "7D_17") (pintype "input"))
      (node (ref "IC8") (pin "17") (pinfunction "7D_17") (pintype "input"))
      (node (ref "IC9") (pin "16") (pinfunction "7Q_16") (pintype "tri_state"))
      (node (ref "SV9") (pin "13") (pinfunction "13_13") (pintype "passive"))
    )
    (net (code "228") (name "PIA-A7") (class "Default")
      (node (ref "IC10") (pin "18") (pinfunction "8D_18") (pintype "input"))
      (node (ref "IC11") (pin "18") (pinfunction "8D_18") (pintype "input"))
      (node (ref "IC12") (pin "18") (pinfunction "8D_18") (pintype "input"))
      (node (ref "IC13") (pin "18") (pinfunction "8D_18") (pintype "input"))
      (node (ref "IC14") (pin "18") (pinfunction "8D_18") (pintype "input"))
      (node (ref "IC15") (pin "19") (pinfunction "8Q_19") (pintype "tri_state"))
      (node (ref "IC16") (pin "19") (pinfunction "8Q_19") (pintype "tri_state"))
      (node (ref "IC2") (pin "19") (pinfunction "8Q_19") (pintype "tri_state"))
      (node (ref "IC25") (pin "11") (pinfunction "B8_11") (pintype "bidirectional"))
      (node (ref "IC3") (pin "19") (pinfunction "8Q_19") (pintype "tri_state"))
      (node (ref "IC4") (pin "19") (pinfunction "8Q_19") (pintype "tri_state"))
      (node (ref "IC6") (pin "18") (pinfunction "8D_18") (pintype "input"))
      (node (ref "IC7") (pin "18") (pinfunction "8D_18") (pintype "input"))
      (node (ref "IC8") (pin "18") (pinfunction "8D_18") (pintype "input"))
      (node (ref "IC9") (pin "19") (pinfunction "8Q_19") (pintype "tri_state"))
      (node (ref "SV9") (pin "15") (pinfunction "15_15") (pintype "passive"))
    )
    (net (code "229") (name "PIA-B0") (class "Default")
      (node (ref "IC1") (pin "23") (pinfunction "A_23") (pintype "input"))
      (node (ref "IC26") (pin "18") (pinfunction "B1_18") (pintype "bidirectional"))
      (node (ref "IC5") (pin "23") (pinfunction "A_23") (pintype "input"))
      (node (ref "SV9") (pin "2") (pinfunction "2_2") (pintype "passive"))
    )
    (net (code "230") (name "PIA-B1") (class "Default")
      (node (ref "IC1") (pin "22") (pinfunction "B_22") (pintype "input"))
      (node (ref "IC26") (pin "17") (pinfunction "B2_17") (pintype "bidirectional"))
      (node (ref "IC5") (pin "22") (pinfunction "B_22") (pintype "input"))
      (node (ref "SV9") (pin "4") (pinfunction "4_4") (pintype "passive"))
    )
    (net (code "231") (name "PIA-B2") (class "Default")
      (node (ref "IC1") (pin "21") (pinfunction "C_21") (pintype "input"))
      (node (ref "IC26") (pin "16") (pinfunction "B3_16") (pintype "bidirectional"))
      (node (ref "IC5") (pin "21") (pinfunction "C_21") (pintype "input"))
      (node (ref "SV9") (pin "6") (pinfunction "6_6") (pintype "passive"))
    )
    (net (code "232") (name "PIA-B3") (class "Default")
      (node (ref "IC1") (pin "20") (pinfunction "D_20") (pintype "input"))
      (node (ref "IC26") (pin "15") (pinfunction "B4_15") (pintype "bidirectional"))
      (node (ref "IC5") (pin "20") (pinfunction "D_20") (pintype "input"))
      (node (ref "SV9") (pin "8") (pinfunction "8_8") (pintype "passive"))
    )
    (net (code "233") (name "PIA-B4") (class "Default")
      (node (ref "IC26") (pin "14") (pinfunction "B5_14") (pintype "bidirectional"))
      (node (ref "IC5") (pin "18") (pinfunction "G1_18") (pintype "input"))
      (node (ref "SV9") (pin "10") (pinfunction "10_10") (pintype "passive"))
    )
    (net (code "234") (name "PIA-B5") (class "Default")
      (node (ref "IC1") (pin "18") (pinfunction "G1_18") (pintype "input"))
      (node (ref "IC26") (pin "13") (pinfunction "B6_13") (pintype "bidirectional"))
      (node (ref "SV9") (pin "12") (pinfunction "12_12") (pintype "passive"))
    )
    (net (code "235") (name "PIA-B6") (class "Default")
      (node (ref "IC26") (pin "12") (pinfunction "B7_12") (pintype "bidirectional"))
      (node (ref "SV9") (pin "14") (pinfunction "14_14") (pintype "passive"))
    )
    (net (code "236") (name "PIA-B7") (class "Default")
      (node (ref "IC26") (pin "11") (pinfunction "B8_11") (pintype "bidirectional"))
      (node (ref "SV9") (pin "16") (pinfunction "16_16") (pintype "passive"))
    )
    (net (code "237") (name "RX") (class "Default")
      (node (ref "IC20") (pin "12") (pinfunction "R1OUT_12") (pintype "output"))
      (node (ref "IC21") (pin "2") (pinfunction "RXDATA_2") (pintype "input"))
    )
    (net (code "238") (name "RXD") (class "Default")
      (node (ref "IC20") (pin "13") (pinfunction "R1IN_13") (pintype "input"))
      (node (ref "X1") (pin "2") (pinfunction "2_2") (pintype "passive"))
    )
    (net (code "239") (name "R{slash}~{W}") (class "Default")
      (node (ref "IC17") (pin "34") (pinfunction "R/~{W}_34") (pintype "output"))
      (node (ref "IC21") (pin "13") (pinfunction "R/~{W}_13") (pintype "input"))
      (node (ref "IC22") (pin "27") (pinfunction "~{PGM}_27") (pintype "input"))
      (node (ref "IC24") (pin "21") (pinfunction "R/~{W}_21") (pintype "input"))
    )
    (net (code "240") (name "TX") (class "Default")
      (node (ref "IC20") (pin "11") (pinfunction "T1IN_11") (pintype "input"))
      (node (ref "IC21") (pin "6") (pinfunction "TXDATA_6") (pintype "output"))
    )
    (net (code "241") (name "TXD") (class "Default")
      (node (ref "IC20") (pin "14") (pinfunction "T1OUT_14") (pintype "output"))
      (node (ref "X1") (pin "3") (pinfunction "3_3") (pintype "passive"))
    )
    (net (code "242") (name "VCC") (class "Default")
      (node (ref "C10") (pin "1") (pinfunction "1_1") (pintype "passive"))
      (node (ref "IC15") (pin "11") (pinfunction "ENC_11") (pintype "input"))
      (node (ref "IC16") (pin "11") (pinfunction "ENC_11") (pintype "input"))
      (node (ref "IC17") (pin "35") (pinfunction "VCCSTB_35") (pintype "input"))
      (node (ref "IC17") (pin "36") (pinfunction "RE_36") (pintype "input"))
      (node (ref "IC17") (pin "8") (pinfunction "VCC_8") (pintype "power_in"))
      (node (ref "IC2") (pin "11") (pinfunction "ENC_11") (pintype "input"))
      (node (ref "IC21") (pin "10") (pinfunction "CS1_10") (pintype "input"))
      (node (ref "IC21") (pin "12") (pinfunction "VCC_12") (pintype "power_in"))
      (node (ref "IC21") (pin "8") (pinfunction "CS0_8") (pintype "input"))
      (node (ref "IC22") (pin "1") (pinfunction "VPP_1") (pintype "input"))
      (node (ref "IC23") (pin "1") (pinfunction "VPP_1") (pintype "input"))
      (node (ref "IC23") (pin "27") (pinfunction "~{PGM}_27") (pintype "input"))
      (node (ref "IC24") (pin "20") (pinfunction "VCC_20") (pintype "power_in"))
      (node (ref "IC24") (pin "22") (pinfunction "CS0_22") (pintype "input"))
      (node (ref "IC24") (pin "24") (pinfunction "CS1_24") (pintype "input"))
      (node (ref "IC27") (pin "10") (pinfunction "R_10") (pintype "input"))
      (node (ref "IC27") (pin "14") (pinfunction "V+_14") (pintype "power_in"))
      (node (ref "IC27") (pin "4") (pinfunction "R_4") (pintype "input"))
      (node (ref "IC28") (pin "6") (pinfunction "G1_6") (pintype "input"))
      (node (ref "IC29") (pin "1") (pinfunction "VPP_1") (pintype "input"))
      (node (ref "IC29") (pin "27") (pinfunction "~{PGM}_27") (pintype "input"))
      (node (ref "IC3") (pin "11") (pinfunction "ENC_11") (pintype "input"))
      (node (ref "IC4") (pin "11") (pinfunction "ENC_11") (pintype "input"))
      (node (ref "IC9") (pin "11") (pinfunction "ENC_11") (pintype "input"))
      (node (ref "JP2") (pin "2") (pinfunction "2_2") (pintype "passive"))
      (node (ref "R1") (pin "2") (pinfunction "2_2") (pintype "passive"))
      (node (ref "R12") (pin "2") (pinfunction "2_2") (pintype "passive"))
      (node (ref "R14") (pin "2") (pinfunction "2_2") (pintype "passive"))
      (node (ref "R2") (pin "2") (pinfunction "2_2") (pintype "passive"))
      (node (ref "R3") (pin "2") (pinfunction "2_2") (pintype "passive"))
      (node (ref "R5") (pin "2") (pinfunction "2_2") (pintype "passive"))
      (node (ref "R6") (pin "2") (pinfunction "2_2") (pintype "passive"))
      (node (ref "R7") (pin "2") (pinfunction "2_2") (pintype "passive"))
      (node (ref "R8") (pin "2") (pinfunction "2_2") (pintype "passive"))
      (node (ref "R9") (pin "2") (pinfunction "2_2") (pintype "passive"))
      (node (ref "SV9") (pin "17") (pinfunction "17_17") (pintype "passive"))
      (node (ref "SV9") (pin "19") (pinfunction "19_19") (pintype "passive"))
    )
    (net (code "243") (name "VMA") (class "Default")
      (node (ref "IC17") (pin "5") (pinfunction "VMA_5") (pintype "output"))
      (node (ref "IC18") (pin "9") (pinfunction "I0_9") (pintype "input"))
    )
    (net (code "244") (name "unconnected-(IC17A-BA-Pad7)") (class "Default")
      (node (ref "IC17") (pin "7") (pinfunction "BA_7") (pintype "output"))
    )
    (net (code "245") (name "unconnected-(IC19A-Y0-Pad15)") (class "Default")
      (node (ref "IC19") (pin "15") (pinfunction "Y0_15") (pintype "output"))
    )
    (net (code "246") (name "unconnected-(IC19A-Y1-Pad14)") (class "Default")
      (node (ref "IC19") (pin "14") (pinfunction "Y1_14") (pintype "output"))
    )
    (net (code "247") (name "unconnected-(IC19A-Y2-Pad13)") (class "Default")
      (node (ref "IC19") (pin "13") (pinfunction "Y2_13") (pintype "output"))
    )
    (net (code "248") (name "unconnected-(IC19A-Y3-Pad12)") (class "Default")
      (node (ref "IC19") (pin "12") (pinfunction "Y3_12") (pintype "output"))
    )
    (net (code "249") (name "unconnected-(IC19A-Y4-Pad11)") (class "Default")
      (node (ref "IC19") (pin "11") (pinfunction "Y4_11") (pintype "output"))
    )
    (net (code "250") (name "unconnected-(IC19A-Y5-Pad10)") (class "Default")
      (node (ref "IC19") (pin "10") (pinfunction "Y5_10") (pintype "output"))
    )
    (net (code "251") (name "unconnected-(IC20A-R2OUT-Pad9)") (class "Default")
      (node (ref "IC20") (pin "9") (pinfunction "R2OUT_9") (pintype "output"))
    )
    (net (code "252") (name "unconnected-(IC28A-Y1-Pad14)") (class "Default")
      (node (ref "IC28") (pin "14") (pinfunction "Y1_14") (pintype "output"))
    )
    (net (code "253") (name "unconnected-(IC28A-Y2-Pad13)") (class "Default")
      (node (ref "IC28") (pin "13") (pinfunction "Y2_13") (pintype "output"))
    )
    (net (code "254") (name "unconnected-(IC28A-Y3-Pad12)") (class "Default")
      (node (ref "IC28") (pin "12") (pinfunction "Y3_12") (pintype "output"))
    )
    (net (code "255") (name "unconnected-(IC28A-Y4-Pad11)") (class "Default")
      (node (ref "IC28") (pin "11") (pinfunction "Y4_11") (pintype "output"))
    )
    (net (code "256") (name "unconnected-(R11-PadS)") (class "Default")
      (node (ref "R11") (pin "S") (pinfunction "S_S") (pintype "passive"))
    )
    (net (code "257") (name "unconnected-(X1-Pad1)") (class "Default")
      (node (ref "X1") (pin "1") (pinfunction "1_1") (pintype "passive"))
    )
    (net (code "258") (name "unconnected-(X1-Pad9)") (class "Default")
      (node (ref "X1") (pin "9") (pinfunction "9_9") (pintype "passive"))
    )
    (net (code "259") (name "~{AB}") (class "Default")
      (node (ref "IC22") (pin "20") (pinfunction "~{CE}_20") (pintype "input"))
      (node (ref "IC22") (pin "22") (pinfunction "~{OE}_22") (pintype "input"))
      (node (ref "IC28") (pin "10") (pinfunction "Y5_10") (pintype "output"))
    )
    (net (code "260") (name "~{CD}") (class "Default")
      (node (ref "IC28") (pin "9") (pinfunction "Y6_9") (pintype "output"))
      (node (ref "IC29") (pin "20") (pinfunction "~{CE}_20") (pintype "input"))
      (node (ref "IC29") (pin "22") (pinfunction "~{OE}_22") (pintype "input"))
    )
    (net (code "261") (name "~{EF}") (class "Default")
      (node (ref "IC23") (pin "20") (pinfunction "~{CE}_20") (pintype "input"))
      (node (ref "IC23") (pin "22") (pinfunction "~{OE}_22") (pintype "input"))
      (node (ref "IC28") (pin "7") (pinfunction "Y7_7") (pintype "output"))
    )
    (net (code "262") (name "~{HLT}") (class "Default")
      (node (ref "IC17") (pin "2") (pinfunction "HALT_2") (pintype "input"))
      (node (ref "R5") (pin "1") (pinfunction "1_1") (pintype "passive"))
    )
    (net (code "263") (name "~{IO-E}") (class "Default")
      (node (ref "IC19") (pin "9") (pinfunction "Y6_9") (pintype "output"))
      (node (ref "IC24") (pin "23") (pinfunction "CS2_23") (pintype "input"))
    )
    (net (code "264") (name "~{IO-F}") (class "Default")
      (node (ref "IC19") (pin "7") (pinfunction "Y7_7") (pintype "output"))
      (node (ref "IC21") (pin "9") (pinfunction "CS2_9") (pintype "input"))
    )
    (net (code "265") (name "~{IRQ}") (class "Default")
      (node (ref "IC17") (pin "4") (pinfunction "IRQ_4") (pintype "input"))
      (node (ref "IC24") (pin "37") (pinfunction "IRQB_37") (pintype "open_collector"))
      (node (ref "IC24") (pin "38") (pinfunction "IRQA_38") (pintype "open_collector"))
      (node (ref "R7") (pin "1") (pinfunction "1_1") (pintype "passive"))
    )
    (net (code "266") (name "~{NMI}") (class "Default")
      (node (ref "IC17") (pin "6") (pinfunction "NMI_6") (pintype "input"))
      (node (ref "IC21") (pin "7") (pinfunction "IRQ_7") (pintype "output"))
      (node (ref "R6") (pin "1") (pinfunction "1_1") (pintype "passive"))
    )
    (net (code "267") (name "~{RST}") (class "Default")
      (node (ref "IC17") (pin "40") (pinfunction "RESET_40") (pintype "input"))
      (node (ref "IC18") (pin "6") (pinfunction "O_6") (pintype "output"))
      (node (ref "IC24") (pin "34") (pinfunction "RESET_34") (pintype "input"))
    )
  )
)
